# dw08aRev2.net
KiCad netlist of a schematic drawn in EAGLE
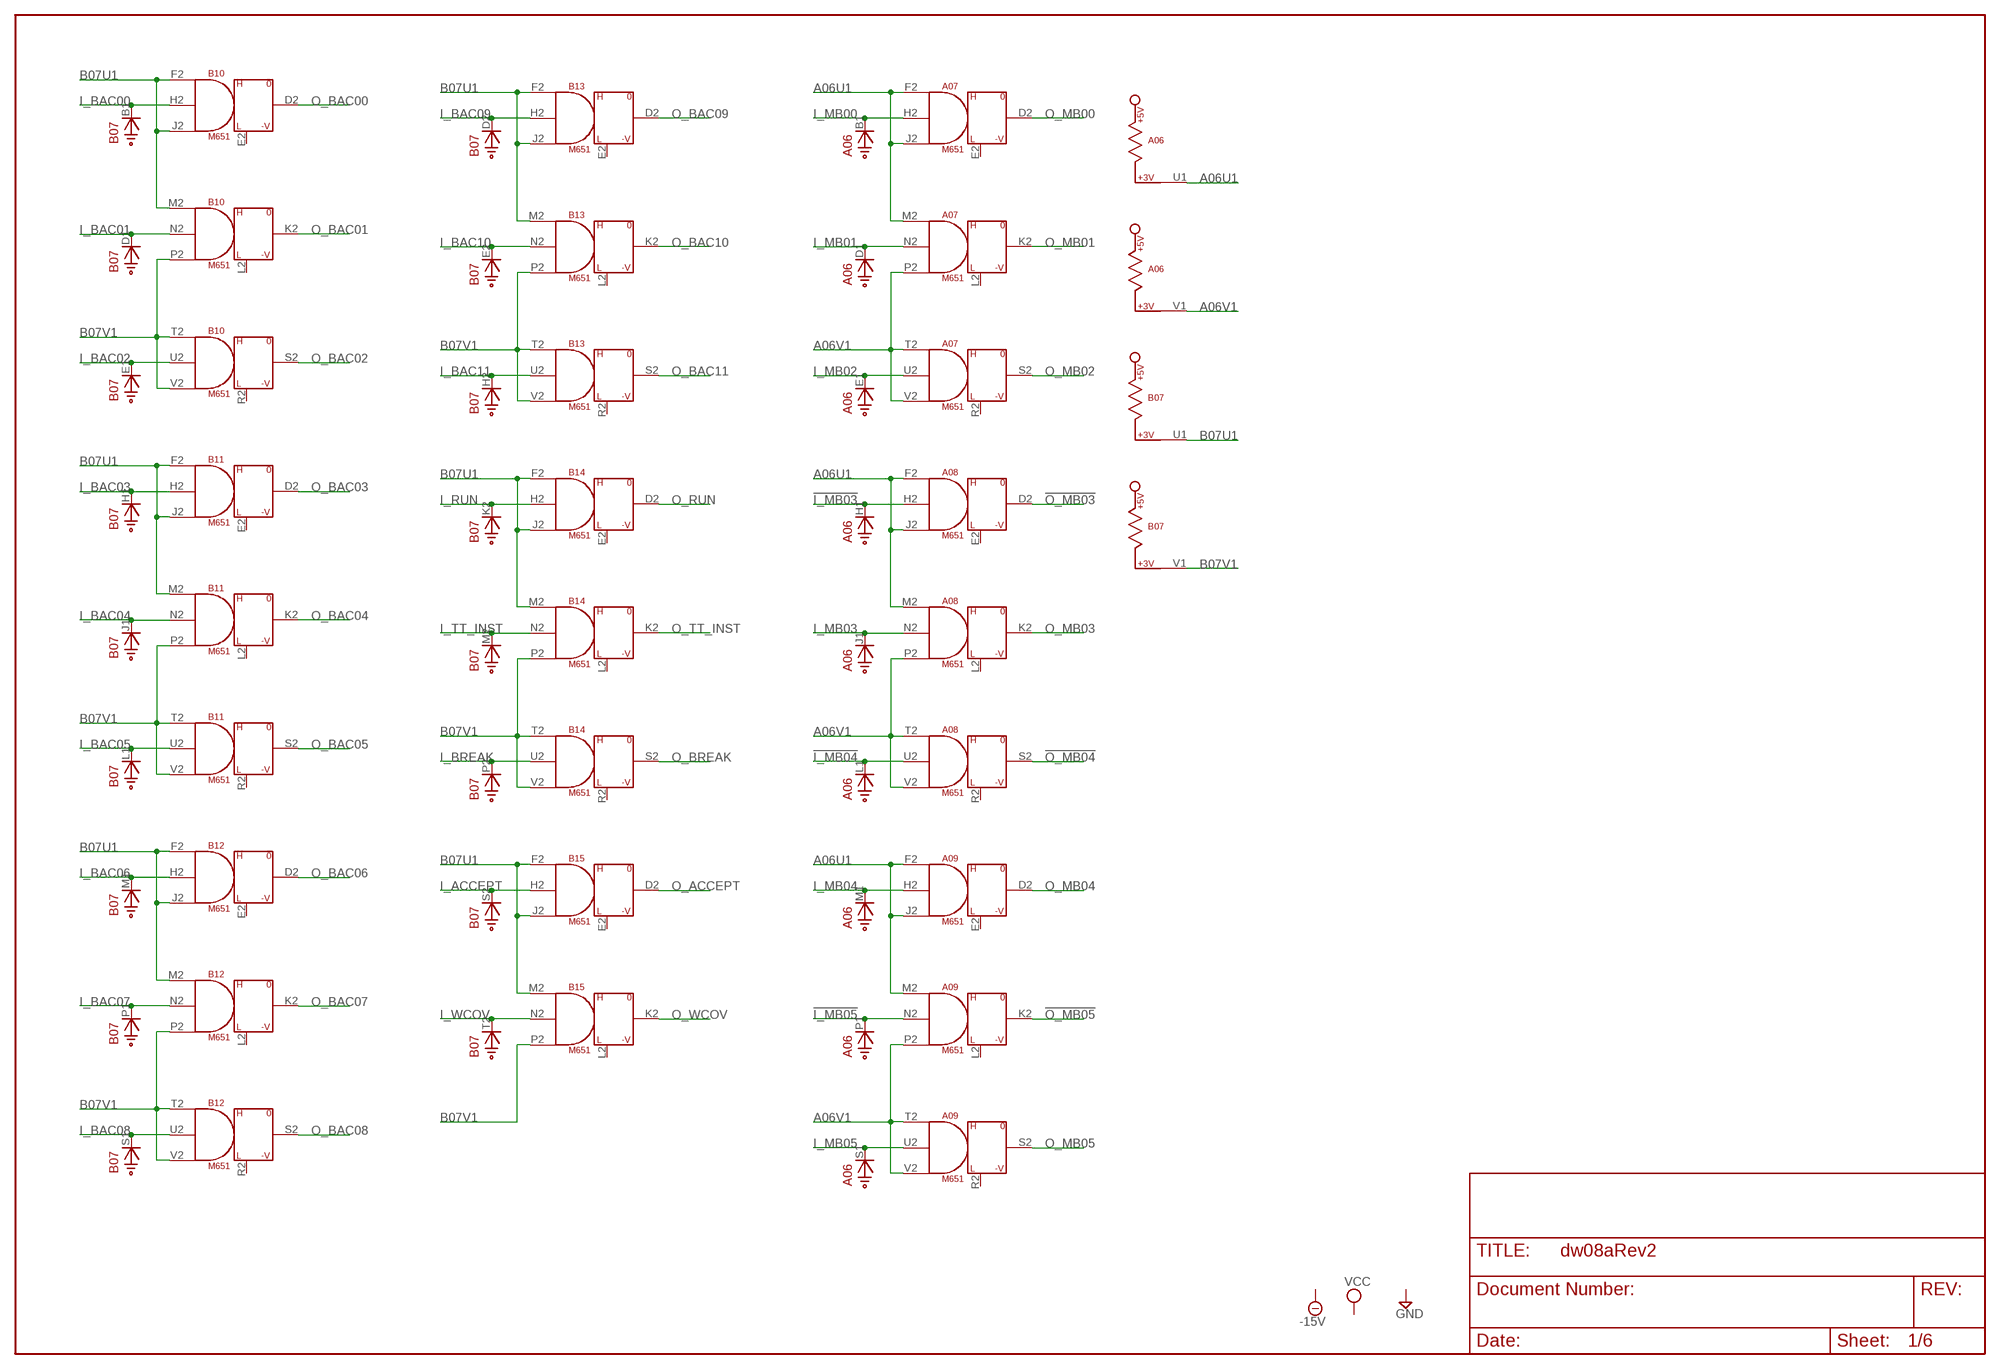
[diagram p0: schematic, sheet 1]
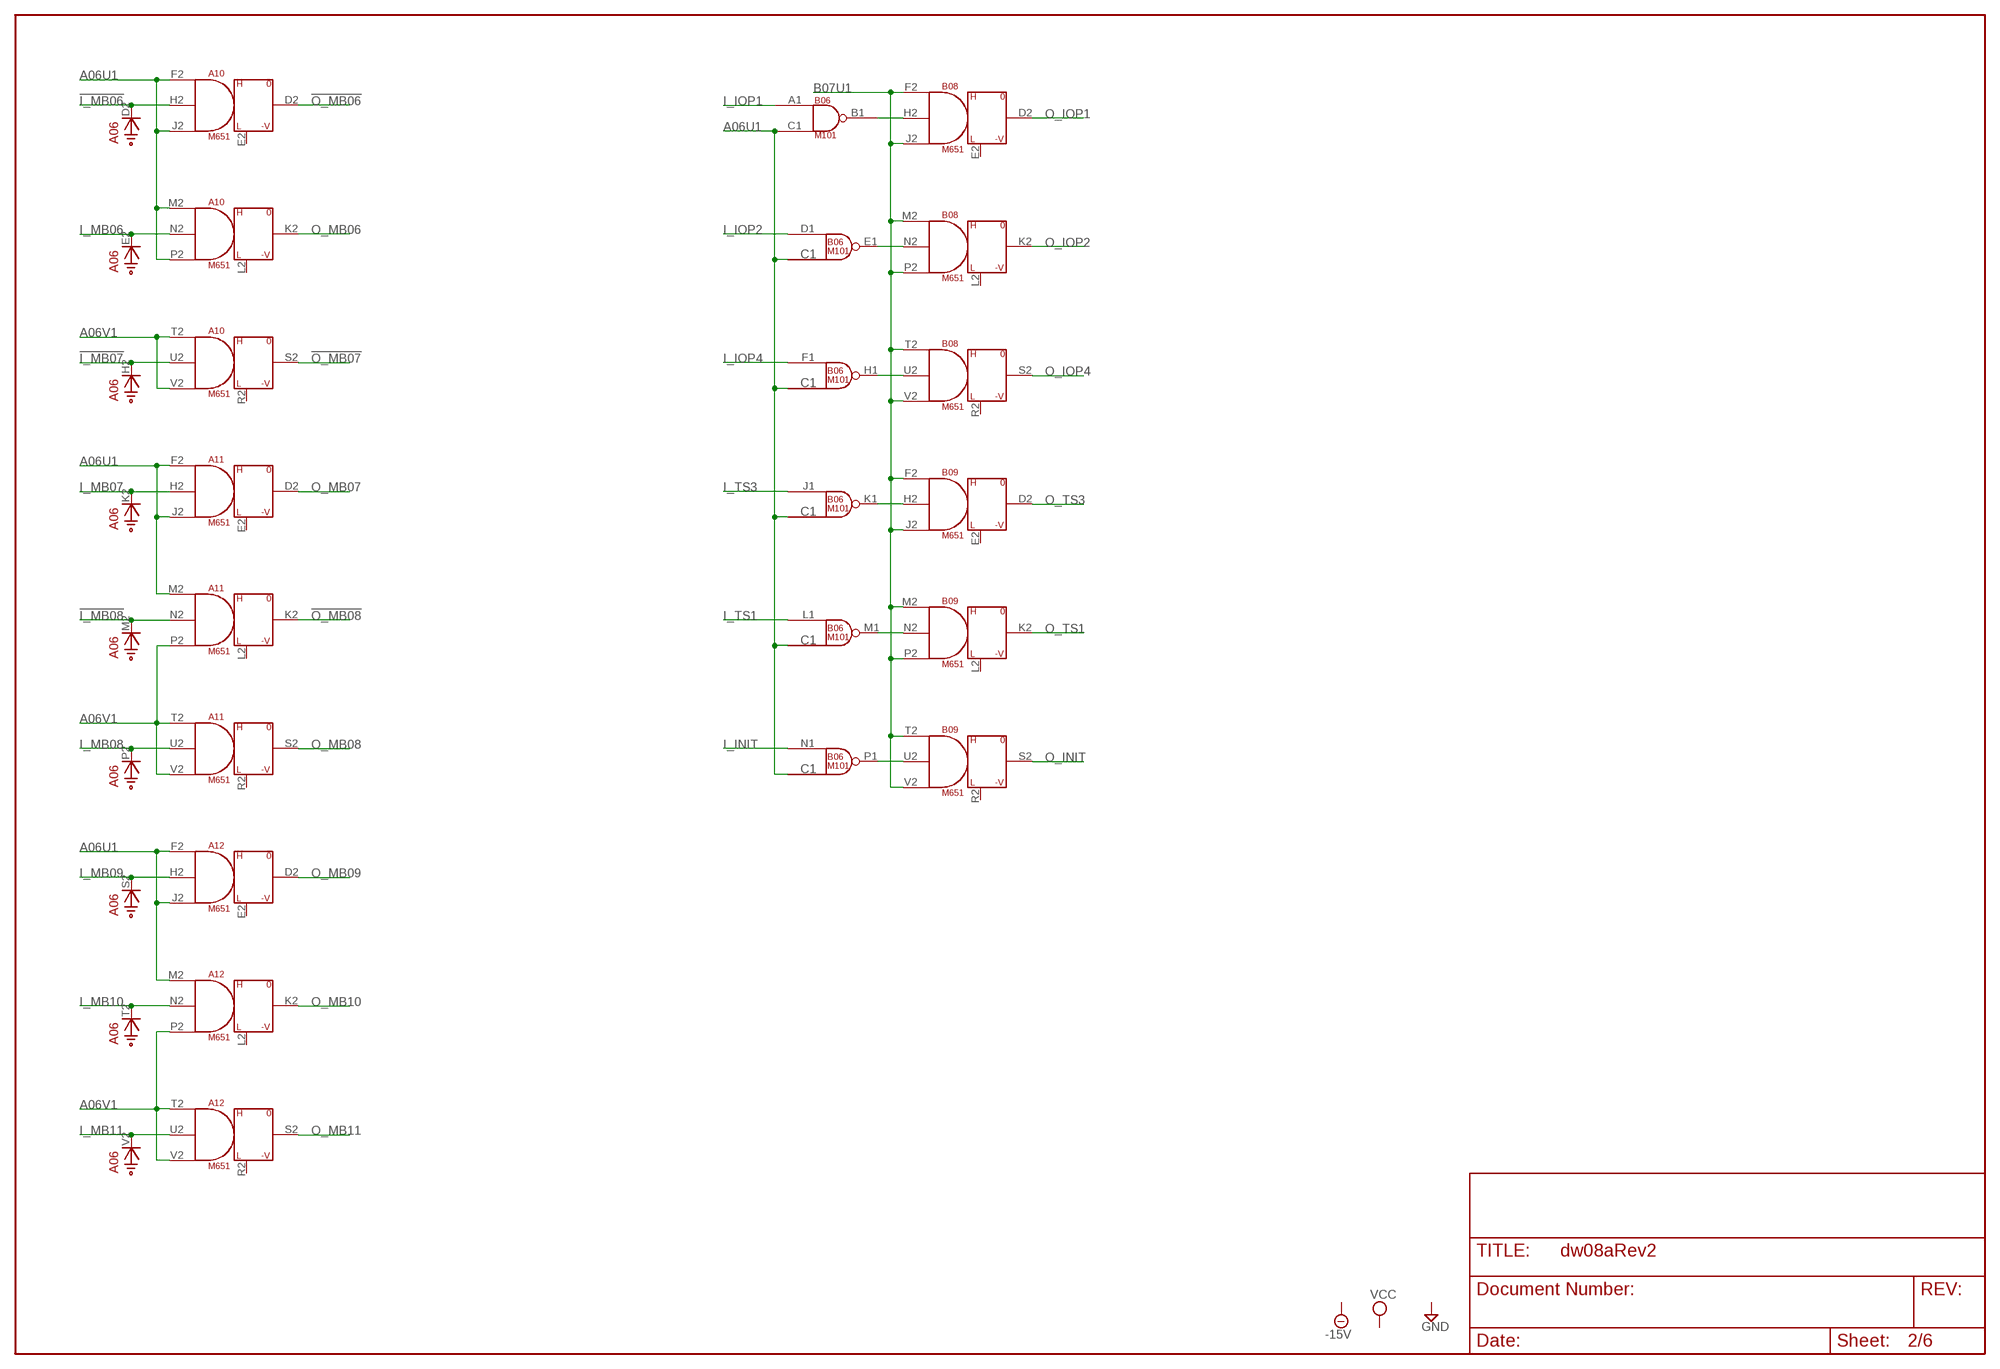
[diagram p1: schematic, sheet 2]
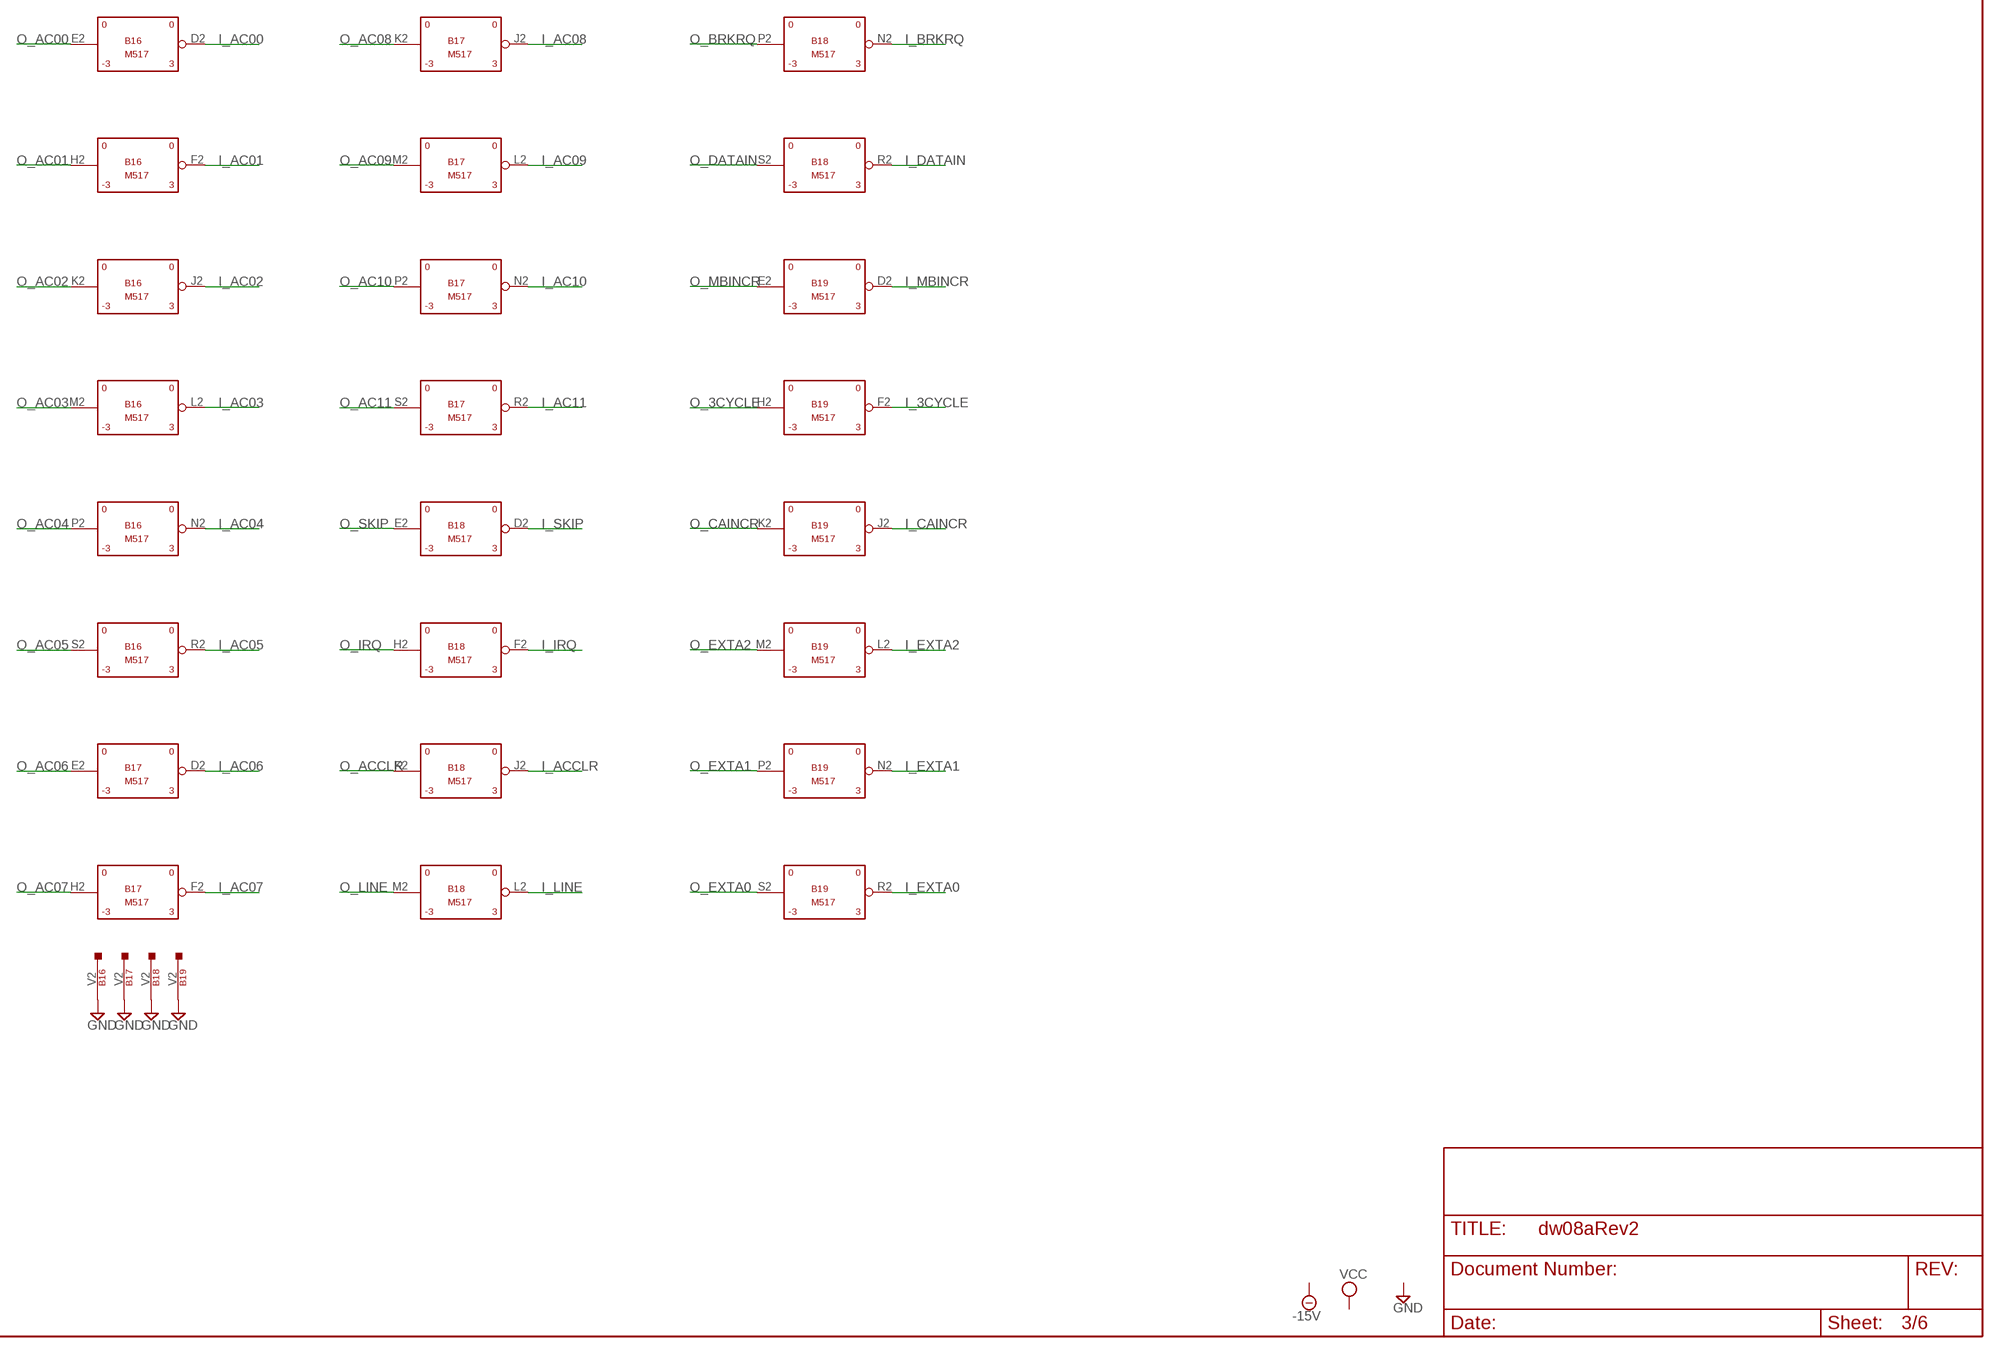
[diagram p2: schematic, sheet 3]
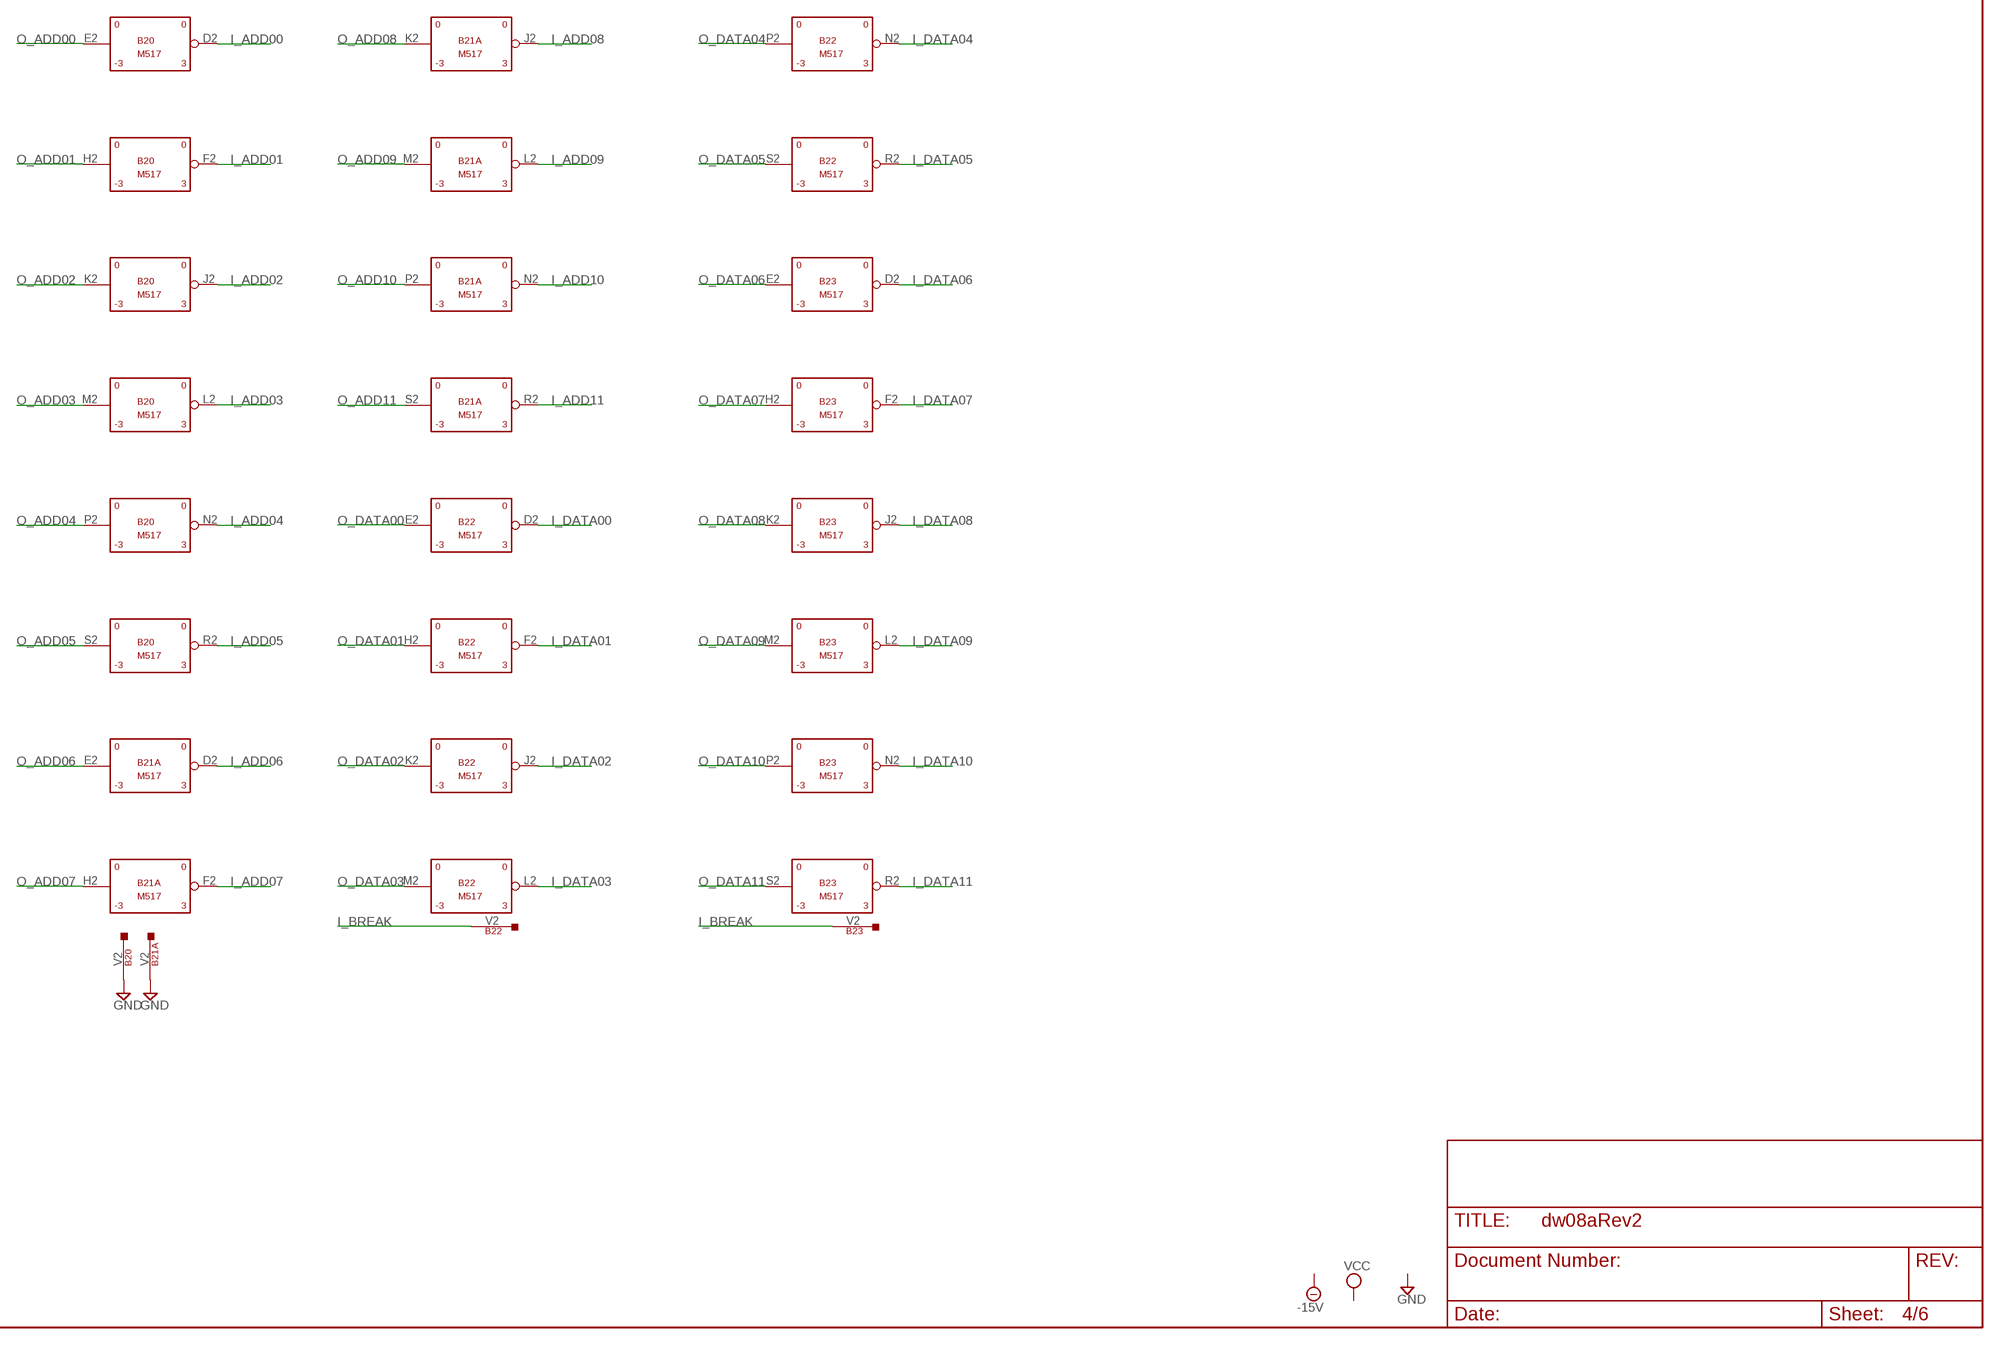
[diagram p3: schematic, sheet 4]
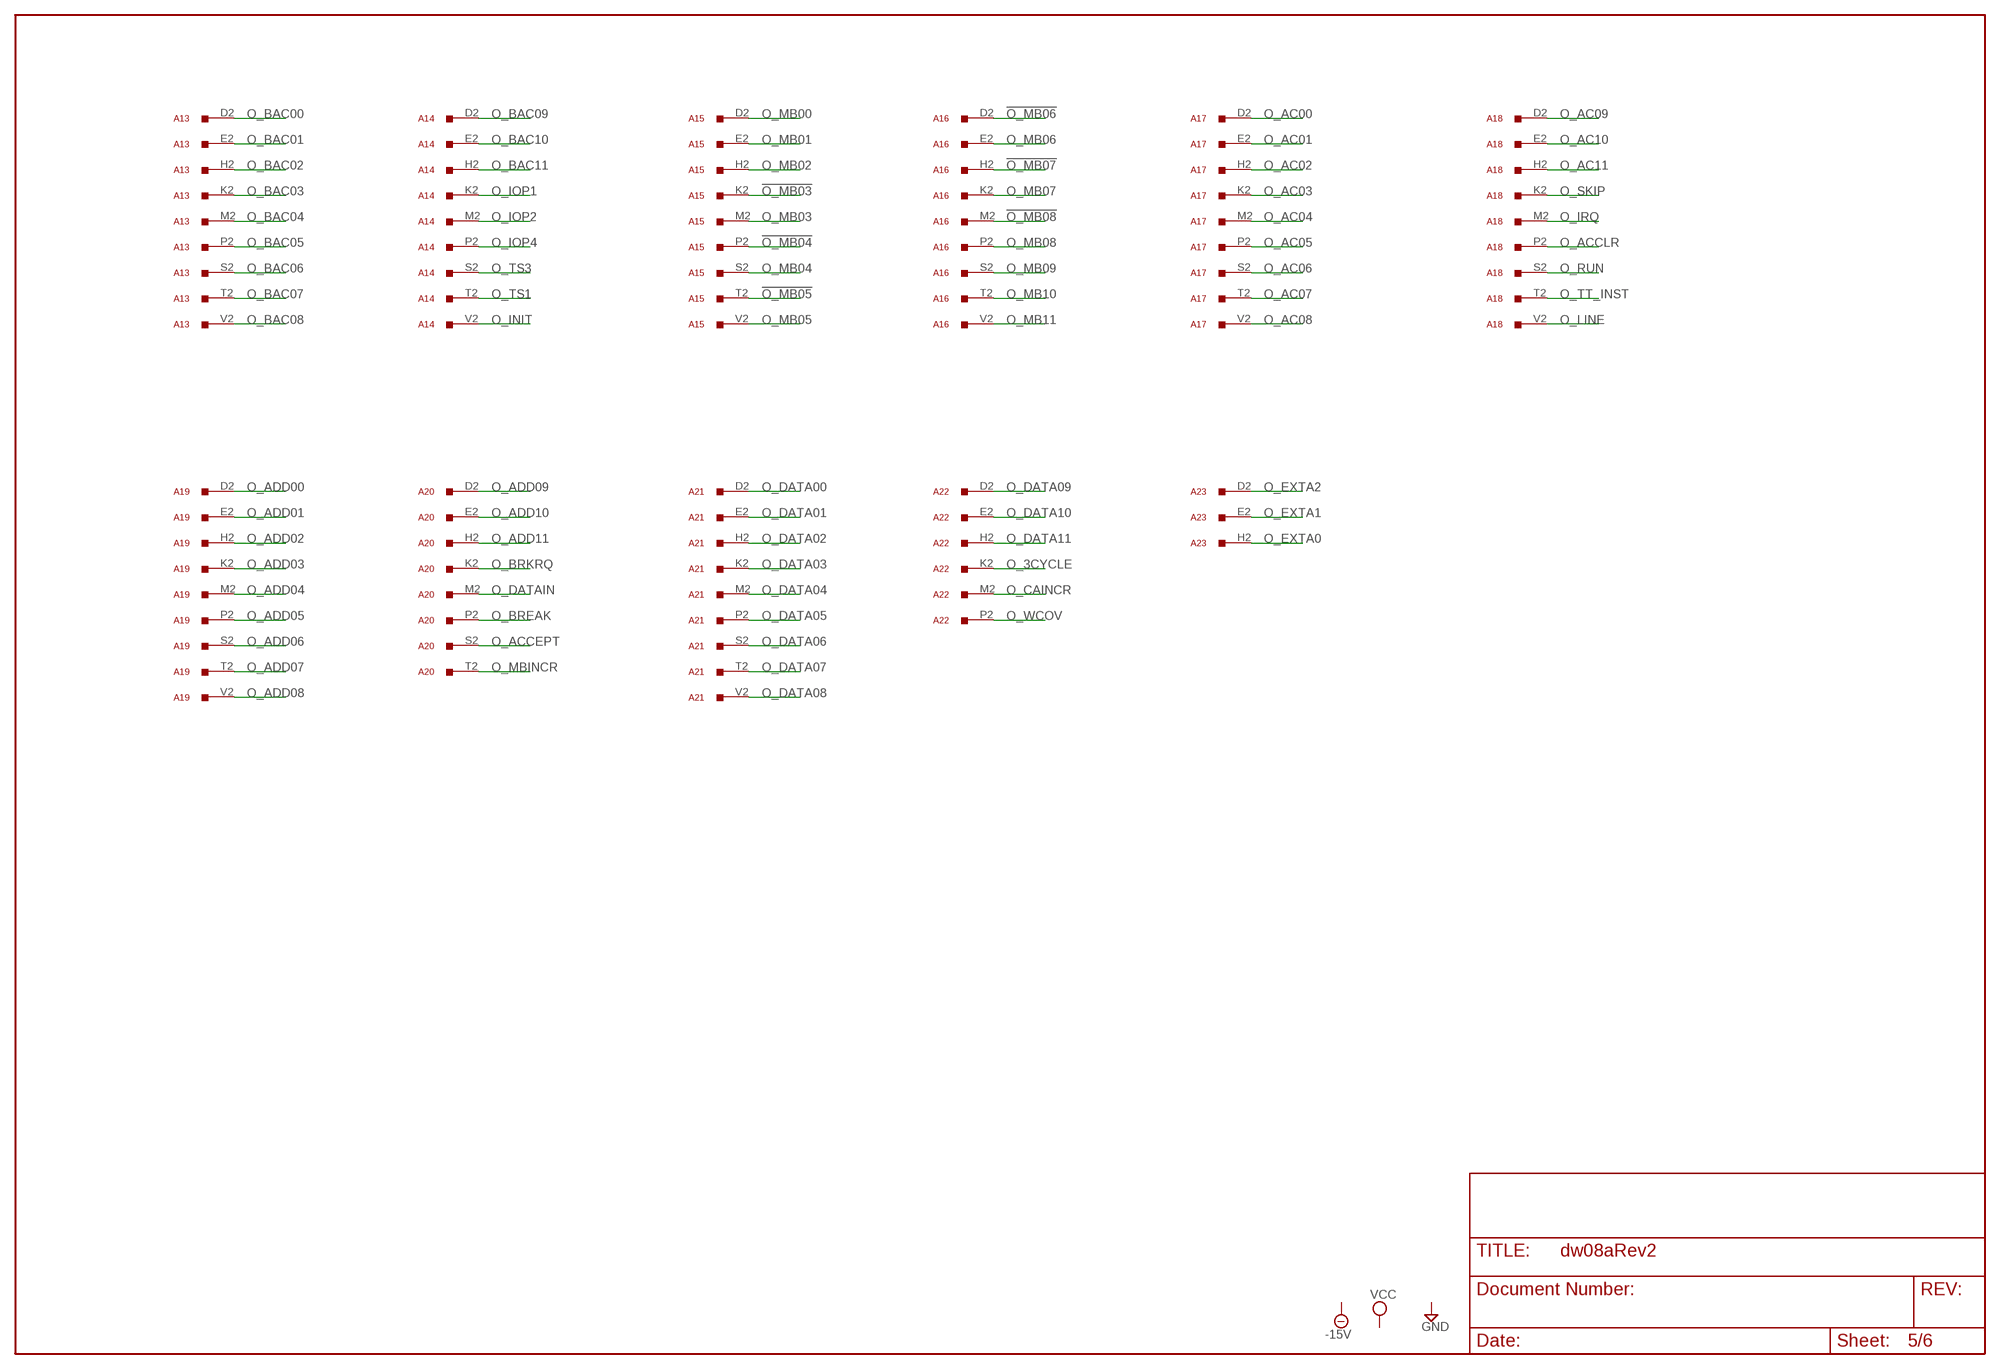
[diagram p4: schematic, sheet 5]
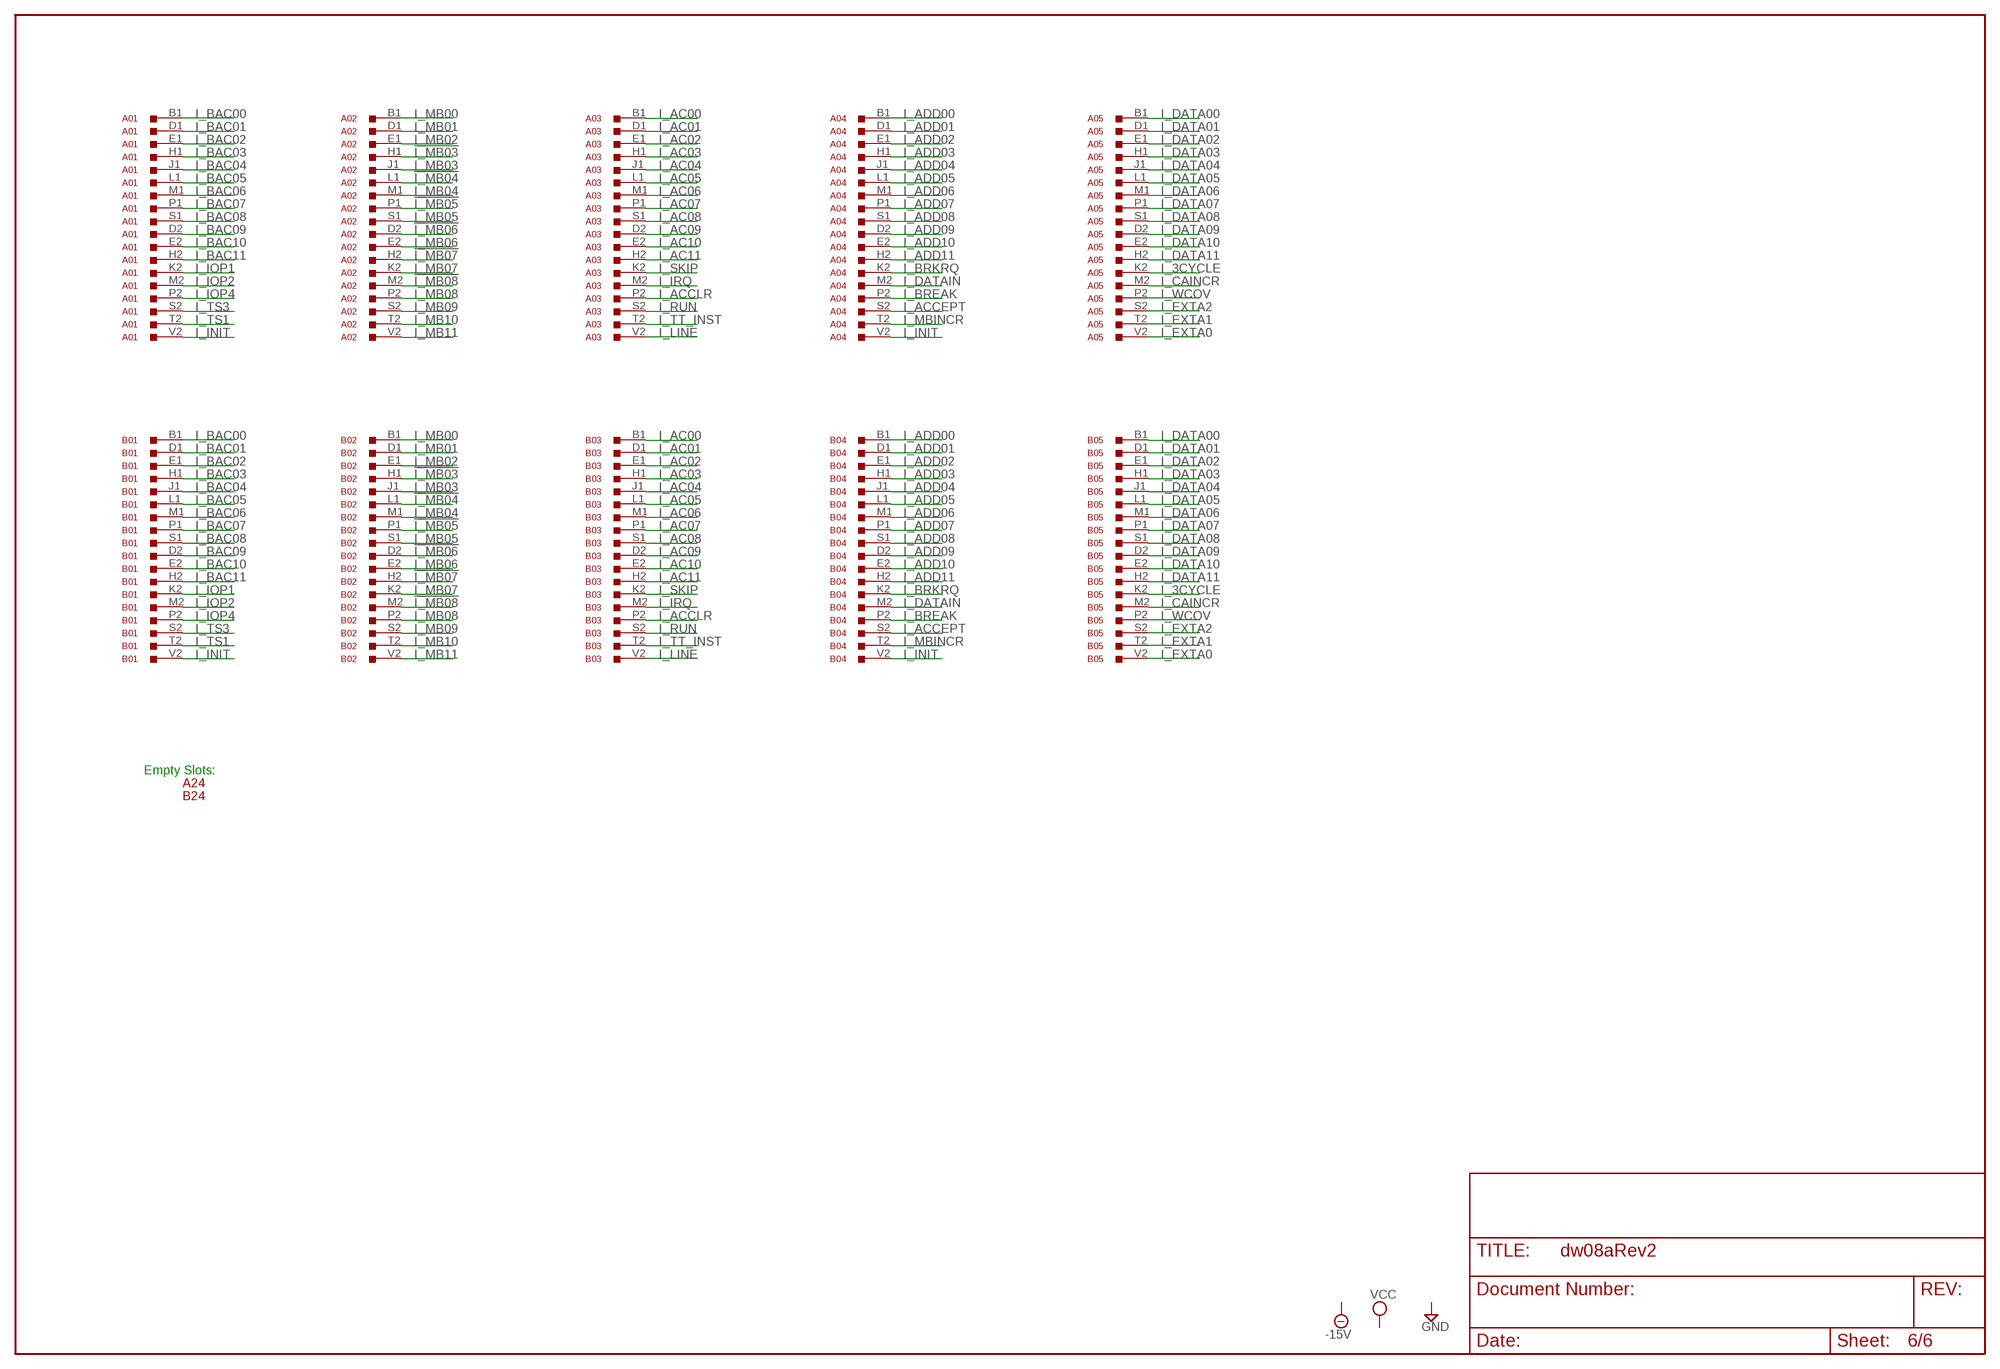
[diagram p5: schematic, sheet 6]

(export (version "E")
  (design (tool "Eeschema 10.0.6"))
  (components
    (comp (ref "A06")
      (value "M907")
      (footprint "eagle-import:H807")
      (libsource (lib "eagle-import") (part "M907"))
    )
    (comp (ref "A07")
      (value "M651")
      (footprint "eagle-import:H807")
      (libsource (lib "eagle-import") (part "M651"))
    )
    (comp (ref "A08")
      (value "M651")
      (footprint "eagle-import:H807")
      (libsource (lib "eagle-import") (part "M651"))
    )
    (comp (ref "A09")
      (value "M651")
      (footprint "eagle-import:H807")
      (libsource (lib "eagle-import") (part "M651"))
    )
    (comp (ref "B07")
      (value "M907")
      (footprint "eagle-import:H807")
      (libsource (lib "eagle-import") (part "M907"))
    )
    (comp (ref "B10")
      (value "M651")
      (footprint "eagle-import:H807")
      (libsource (lib "eagle-import") (part "M651"))
    )
    (comp (ref "B11")
      (value "M651")
      (footprint "eagle-import:H807")
      (libsource (lib "eagle-import") (part "M651"))
    )
    (comp (ref "B12")
      (value "M651")
      (footprint "eagle-import:H807")
      (libsource (lib "eagle-import") (part "M651"))
    )
    (comp (ref "B13")
      (value "M651")
      (footprint "eagle-import:H807")
      (libsource (lib "eagle-import") (part "M651"))
    )
    (comp (ref "B14")
      (value "M651")
      (footprint "eagle-import:H807")
      (libsource (lib "eagle-import") (part "M651"))
    )
    (comp (ref "B15")
      (value "M651")
      (footprint "eagle-import:H807")
      (libsource (lib "eagle-import") (part "M651"))
    )
    (comp (ref "A10")
      (value "M651")
      (footprint "eagle-import:H807")
      (libsource (lib "eagle-import") (part "M651"))
    )
    (comp (ref "A11")
      (value "M651")
      (footprint "eagle-import:H807")
      (libsource (lib "eagle-import") (part "M651"))
    )
    (comp (ref "A12")
      (value "M651")
      (footprint "eagle-import:H807")
      (libsource (lib "eagle-import") (part "M651"))
    )
    (comp (ref "B06")
      (value "M101")
      (footprint "eagle-import:H807")
      (libsource (lib "eagle-import") (part "M101"))
    )
    (comp (ref "B08")
      (value "M651")
      (footprint "eagle-import:H807")
      (libsource (lib "eagle-import") (part "M651"))
    )
    (comp (ref "B09")
      (value "M651")
      (footprint "eagle-import:H807")
      (libsource (lib "eagle-import") (part "M651"))
    )
    (comp (ref "B16")
      (value "M517")
      (footprint "eagle-import:H807")
      (libsource (lib "eagle-import") (part "M517"))
    )
    (comp (ref "B17")
      (value "M517")
      (footprint "eagle-import:H807")
      (libsource (lib "eagle-import") (part "M517"))
    )
    (comp (ref "B18")
      (value "M517")
      (footprint "eagle-import:H807")
      (libsource (lib "eagle-import") (part "M517"))
    )
    (comp (ref "B19")
      (value "M517")
      (footprint "eagle-import:H807")
      (libsource (lib "eagle-import") (part "M517"))
    )
    (comp (ref "A13")
      (value "W011")
      (footprint "eagle-import:H807")
      (libsource (lib "eagle-import") (part "W011"))
    )
    (comp (ref "A14")
      (value "W011")
      (footprint "eagle-import:H807")
      (libsource (lib "eagle-import") (part "W011"))
    )
    (comp (ref "A15")
      (value "W011")
      (footprint "eagle-import:H807")
      (libsource (lib "eagle-import") (part "W011"))
    )
    (comp (ref "A16")
      (value "W011")
      (footprint "eagle-import:H807")
      (libsource (lib "eagle-import") (part "W011"))
    )
    (comp (ref "A17")
      (value "W011")
      (footprint "eagle-import:H807")
      (libsource (lib "eagle-import") (part "W011"))
    )
    (comp (ref "A18")
      (value "W011")
      (footprint "eagle-import:H807")
      (libsource (lib "eagle-import") (part "W011"))
    )
    (comp (ref "A19")
      (value "W011")
      (footprint "eagle-import:H807")
      (libsource (lib "eagle-import") (part "W011"))
    )
    (comp (ref "A20")
      (value "W011")
      (footprint "eagle-import:H807")
      (libsource (lib "eagle-import") (part "W011"))
    )
    (comp (ref "A21")
      (value "W011")
      (footprint "eagle-import:H807")
      (libsource (lib "eagle-import") (part "W011"))
    )
    (comp (ref "A22")
      (value "W011")
      (footprint "eagle-import:H807")
      (libsource (lib "eagle-import") (part "W011"))
    )
    (comp (ref "A23")
      (value "W011")
      (footprint "eagle-import:H807")
      (libsource (lib "eagle-import") (part "W011"))
    )
    (comp (ref "A01")
      (value "M903")
      (footprint "eagle-import:H807")
      (libsource (lib "eagle-import") (part "M903"))
    )
    (comp (ref "A02")
      (value "M903")
      (footprint "eagle-import:H807")
      (libsource (lib "eagle-import") (part "M903"))
    )
    (comp (ref "A03")
      (value "M903")
      (footprint "eagle-import:H807")
      (libsource (lib "eagle-import") (part "M903"))
    )
    (comp (ref "A04")
      (value "M903")
      (footprint "eagle-import:H807")
      (libsource (lib "eagle-import") (part "M903"))
    )
    (comp (ref "A05")
      (value "M903")
      (footprint "eagle-import:H807")
      (libsource (lib "eagle-import") (part "M903"))
    )
    (comp (ref "A24")
      (value "H807")
      (footprint "eagle-import:H807")
      (libsource (lib "eagle-import") (part "H807"))
    )
    (comp (ref "B01")
      (value "M903")
      (footprint "eagle-import:H807")
      (libsource (lib "eagle-import") (part "M903"))
    )
    (comp (ref "B02")
      (value "M903")
      (footprint "eagle-import:H807")
      (libsource (lib "eagle-import") (part "M903"))
    )
    (comp (ref "B03")
      (value "M903")
      (footprint "eagle-import:H807")
      (libsource (lib "eagle-import") (part "M903"))
    )
    (comp (ref "B04")
      (value "M903")
      (footprint "eagle-import:H807")
      (libsource (lib "eagle-import") (part "M903"))
    )
    (comp (ref "B05")
      (value "M903")
      (footprint "eagle-import:H807")
      (libsource (lib "eagle-import") (part "M903"))
    )
    (comp (ref "B24")
      (value "H807")
      (footprint "eagle-import:H807")
      (libsource (lib "eagle-import") (part "H807"))
    )
    (comp (ref "B20")
      (value "M517")
      (footprint "eagle-import:H807")
      (libsource (lib "eagle-import") (part "M517"))
    )
    (comp (ref "B21A")
      (value "M517")
      (footprint "eagle-import:H807")
      (libsource (lib "eagle-import") (part "M517"))
    )
    (comp (ref "B22")
      (value "M517")
      (footprint "eagle-import:H807")
      (libsource (lib "eagle-import") (part "M517"))
    )
    (comp (ref "B23")
      (value "M517")
      (footprint "eagle-import:H807")
      (libsource (lib "eagle-import") (part "M517"))
    )
  )
  (nets
    (net (code "2") (name "A06U1") (class "Default")
      (node (ref "A06") (pin "U1") (pinfunction "P$1_U1") (pintype "passive"))
      (node (ref "A07") (pin "F2") (pinfunction "IN1_F2") (pintype "input"))
      (node (ref "A07") (pin "J2") (pinfunction "IN3_J2") (pintype "input"))
      (node (ref "A07") (pin "M2") (pinfunction "IN1_M2") (pintype "input"))
      (node (ref "A08") (pin "F2") (pinfunction "IN1_F2") (pintype "input"))
      (node (ref "A08") (pin "J2") (pinfunction "IN3_J2") (pintype "input"))
      (node (ref "A08") (pin "M2") (pinfunction "IN1_M2") (pintype "input"))
      (node (ref "A09") (pin "F2") (pinfunction "IN1_F2") (pintype "input"))
      (node (ref "A09") (pin "J2") (pinfunction "IN3_J2") (pintype "input"))
      (node (ref "A09") (pin "M2") (pinfunction "IN1_M2") (pintype "input"))
      (node (ref "A10") (pin "F2") (pinfunction "IN1_F2") (pintype "input"))
      (node (ref "A10") (pin "J2") (pinfunction "IN3_J2") (pintype "input"))
      (node (ref "A10") (pin "M2") (pinfunction "IN1_M2") (pintype "input"))
      (node (ref "A10") (pin "P2") (pinfunction "IN3_P2") (pintype "input"))
      (node (ref "A11") (pin "F2") (pinfunction "IN1_F2") (pintype "input"))
      (node (ref "A11") (pin "J2") (pinfunction "IN3_J2") (pintype "input"))
      (node (ref "A11") (pin "M2") (pinfunction "IN1_M2") (pintype "input"))
      (node (ref "A12") (pin "F2") (pinfunction "IN1_F2") (pintype "input"))
      (node (ref "A12") (pin "J2") (pinfunction "IN3_J2") (pintype "input"))
      (node (ref "A12") (pin "M2") (pinfunction "IN1_M2") (pintype "input"))
      (node (ref "B06") (pin "C1") (pinfunction "IN2_C1") (pintype "input"))
    )
    (net (code "3") (name "A06V1") (class "Default")
      (node (ref "A06") (pin "V1") (pinfunction "P$1_V1") (pintype "passive"))
      (node (ref "A07") (pin "P2") (pinfunction "IN3_P2") (pintype "input"))
      (node (ref "A07") (pin "T2") (pinfunction "IN1_T2") (pintype "input"))
      (node (ref "A07") (pin "V2") (pinfunction "IN3_V2") (pintype "input"))
      (node (ref "A08") (pin "P2") (pinfunction "IN3_P2") (pintype "input"))
      (node (ref "A08") (pin "T2") (pinfunction "IN1_T2") (pintype "input"))
      (node (ref "A08") (pin "V2") (pinfunction "IN3_V2") (pintype "input"))
      (node (ref "A09") (pin "P2") (pinfunction "IN3_P2") (pintype "input"))
      (node (ref "A09") (pin "T2") (pinfunction "IN1_T2") (pintype "input"))
      (node (ref "A09") (pin "V2") (pinfunction "IN3_V2") (pintype "input"))
      (node (ref "A10") (pin "T2") (pinfunction "IN1_T2") (pintype "input"))
      (node (ref "A10") (pin "V2") (pinfunction "IN3_V2") (pintype "input"))
      (node (ref "A11") (pin "P2") (pinfunction "IN3_P2") (pintype "input"))
      (node (ref "A11") (pin "T2") (pinfunction "IN1_T2") (pintype "input"))
      (node (ref "A11") (pin "V2") (pinfunction "IN3_V2") (pintype "input"))
      (node (ref "A12") (pin "P2") (pinfunction "IN3_P2") (pintype "input"))
      (node (ref "A12") (pin "T2") (pinfunction "IN1_T2") (pintype "input"))
      (node (ref "A12") (pin "V2") (pinfunction "IN3_V2") (pintype "input"))
    )
    (net (code "4") (name "B07U1") (class "Default")
      (node (ref "B07") (pin "U1") (pinfunction "P$1_U1") (pintype "passive"))
      (node (ref "B08") (pin "F2") (pinfunction "IN1_F2") (pintype "input"))
      (node (ref "B08") (pin "J2") (pinfunction "IN3_J2") (pintype "input"))
      (node (ref "B08") (pin "M2") (pinfunction "IN1_M2") (pintype "input"))
      (node (ref "B08") (pin "P2") (pinfunction "IN3_P2") (pintype "input"))
      (node (ref "B08") (pin "T2") (pinfunction "IN1_T2") (pintype "input"))
      (node (ref "B08") (pin "V2") (pinfunction "IN3_V2") (pintype "input"))
      (node (ref "B09") (pin "F2") (pinfunction "IN1_F2") (pintype "input"))
      (node (ref "B09") (pin "J2") (pinfunction "IN3_J2") (pintype "input"))
      (node (ref "B09") (pin "M2") (pinfunction "IN1_M2") (pintype "input"))
      (node (ref "B09") (pin "P2") (pinfunction "IN3_P2") (pintype "input"))
      (node (ref "B09") (pin "T2") (pinfunction "IN1_T2") (pintype "input"))
      (node (ref "B09") (pin "V2") (pinfunction "IN3_V2") (pintype "input"))
      (node (ref "B10") (pin "F2") (pinfunction "IN1_F2") (pintype "input"))
      (node (ref "B10") (pin "J2") (pinfunction "IN3_J2") (pintype "input"))
      (node (ref "B10") (pin "M2") (pinfunction "IN1_M2") (pintype "input"))
      (node (ref "B11") (pin "F2") (pinfunction "IN1_F2") (pintype "input"))
      (node (ref "B11") (pin "J2") (pinfunction "IN3_J2") (pintype "input"))
      (node (ref "B11") (pin "M2") (pinfunction "IN1_M2") (pintype "input"))
      (node (ref "B12") (pin "F2") (pinfunction "IN1_F2") (pintype "input"))
      (node (ref "B12") (pin "J2") (pinfunction "IN3_J2") (pintype "input"))
      (node (ref "B12") (pin "M2") (pinfunction "IN1_M2") (pintype "input"))
      (node (ref "B13") (pin "F2") (pinfunction "IN1_F2") (pintype "input"))
      (node (ref "B13") (pin "J2") (pinfunction "IN3_J2") (pintype "input"))
      (node (ref "B13") (pin "M2") (pinfunction "IN1_M2") (pintype "input"))
      (node (ref "B14") (pin "F2") (pinfunction "IN1_F2") (pintype "input"))
      (node (ref "B14") (pin "J2") (pinfunction "IN3_J2") (pintype "input"))
      (node (ref "B14") (pin "M2") (pinfunction "IN1_M2") (pintype "input"))
      (node (ref "B15") (pin "F2") (pinfunction "IN1_F2") (pintype "input"))
      (node (ref "B15") (pin "J2") (pinfunction "IN3_J2") (pintype "input"))
      (node (ref "B15") (pin "M2") (pinfunction "IN1_M2") (pintype "input"))
    )
    (net (code "5") (name "B07V1") (class "Default")
      (node (ref "B07") (pin "V1") (pinfunction "P$1_V1") (pintype "passive"))
      (node (ref "B10") (pin "P2") (pinfunction "IN3_P2") (pintype "input"))
      (node (ref "B10") (pin "T2") (pinfunction "IN1_T2") (pintype "input"))
      (node (ref "B10") (pin "V2") (pinfunction "IN3_V2") (pintype "input"))
      (node (ref "B11") (pin "P2") (pinfunction "IN3_P2") (pintype "input"))
      (node (ref "B11") (pin "T2") (pinfunction "IN1_T2") (pintype "input"))
      (node (ref "B11") (pin "V2") (pinfunction "IN3_V2") (pintype "input"))
      (node (ref "B12") (pin "P2") (pinfunction "IN3_P2") (pintype "input"))
      (node (ref "B12") (pin "T2") (pinfunction "IN1_T2") (pintype "input"))
      (node (ref "B12") (pin "V2") (pinfunction "IN3_V2") (pintype "input"))
      (node (ref "B13") (pin "P2") (pinfunction "IN3_P2") (pintype "input"))
      (node (ref "B13") (pin "T2") (pinfunction "IN1_T2") (pintype "input"))
      (node (ref "B13") (pin "V2") (pinfunction "IN3_V2") (pintype "input"))
      (node (ref "B14") (pin "P2") (pinfunction "IN3_P2") (pintype "input"))
      (node (ref "B14") (pin "T2") (pinfunction "IN1_T2") (pintype "input"))
      (node (ref "B14") (pin "V2") (pinfunction "IN3_V2") (pintype "input"))
      (node (ref "B15") (pin "P2") (pinfunction "IN3_P2") (pintype "input"))
    )
    (net (code "6") (name "GND") (class "Default")
      (node (ref "B16") (pin "V2") (pinfunction "P$1_V2") (pintype "input"))
      (node (ref "B17") (pin "V2") (pinfunction "P$1_V2") (pintype "input"))
      (node (ref "B18") (pin "V2") (pinfunction "P$1_V2") (pintype "input"))
      (node (ref "B19") (pin "V2") (pinfunction "P$1_V2") (pintype "input"))
      (node (ref "B20") (pin "V2") (pinfunction "P$1_V2") (pintype "input"))
      (node (ref "B21A") (pin "V2") (pinfunction "P$1_V2") (pintype "input"))
    )
    (net (code "7") (name "I_3CYCLE") (class "Default")
      (node (ref "A05") (pin "K2") (pinfunction "P$2_K2") (pintype "bidirectional"))
      (node (ref "B05") (pin "K2") (pinfunction "P$2_K2") (pintype "bidirectional"))
      (node (ref "B19") (pin "F2") (pinfunction "OUT_F2") (pintype "output"))
    )
    (net (code "8") (name "I_AC00") (class "Default")
      (node (ref "A03") (pin "B1") (pinfunction "P$2_B1") (pintype "bidirectional"))
      (node (ref "B03") (pin "B1") (pinfunction "P$2_B1") (pintype "bidirectional"))
      (node (ref "B16") (pin "D2") (pinfunction "OUT_D2") (pintype "output"))
    )
    (net (code "9") (name "I_AC01") (class "Default")
      (node (ref "A03") (pin "D1") (pinfunction "P$2_D1") (pintype "bidirectional"))
      (node (ref "B03") (pin "D1") (pinfunction "P$2_D1") (pintype "bidirectional"))
      (node (ref "B16") (pin "F2") (pinfunction "OUT_F2") (pintype "output"))
    )
    (net (code "10") (name "I_AC02") (class "Default")
      (node (ref "A03") (pin "E1") (pinfunction "P$2_E1") (pintype "bidirectional"))
      (node (ref "B03") (pin "E1") (pinfunction "P$2_E1") (pintype "bidirectional"))
      (node (ref "B16") (pin "J2") (pinfunction "OUT_J2") (pintype "output"))
    )
    (net (code "11") (name "I_AC03") (class "Default")
      (node (ref "A03") (pin "H1") (pinfunction "P$2_H1") (pintype "bidirectional"))
      (node (ref "B03") (pin "H1") (pinfunction "P$2_H1") (pintype "bidirectional"))
      (node (ref "B16") (pin "L2") (pinfunction "OUT_L2") (pintype "output"))
    )
    (net (code "12") (name "I_AC04") (class "Default")
      (node (ref "A03") (pin "J1") (pinfunction "P$2_J1") (pintype "bidirectional"))
      (node (ref "B03") (pin "J1") (pinfunction "P$2_J1") (pintype "bidirectional"))
      (node (ref "B16") (pin "N2") (pinfunction "OUT_N2") (pintype "output"))
    )
    (net (code "13") (name "I_AC05") (class "Default")
      (node (ref "A03") (pin "L1") (pinfunction "P$2_L1") (pintype "bidirectional"))
      (node (ref "B03") (pin "L1") (pinfunction "P$2_L1") (pintype "bidirectional"))
      (node (ref "B16") (pin "R2") (pinfunction "OUT_R2") (pintype "output"))
    )
    (net (code "14") (name "I_AC06") (class "Default")
      (node (ref "A03") (pin "M1") (pinfunction "P$2_M1") (pintype "bidirectional"))
      (node (ref "B03") (pin "M1") (pinfunction "P$2_M1") (pintype "bidirectional"))
      (node (ref "B17") (pin "D2") (pinfunction "OUT_D2") (pintype "output"))
    )
    (net (code "15") (name "I_AC07") (class "Default")
      (node (ref "A03") (pin "P1") (pinfunction "P$2_P1") (pintype "bidirectional"))
      (node (ref "B03") (pin "P1") (pinfunction "P$2_P1") (pintype "bidirectional"))
      (node (ref "B17") (pin "F2") (pinfunction "OUT_F2") (pintype "output"))
    )
    (net (code "16") (name "I_AC08") (class "Default")
      (node (ref "A03") (pin "S1") (pinfunction "P$2_S1") (pintype "bidirectional"))
      (node (ref "B03") (pin "S1") (pinfunction "P$2_S1") (pintype "bidirectional"))
      (node (ref "B17") (pin "J2") (pinfunction "OUT_J2") (pintype "output"))
    )
    (net (code "17") (name "I_AC09") (class "Default")
      (node (ref "A03") (pin "D2") (pinfunction "P$2_D2") (pintype "bidirectional"))
      (node (ref "B03") (pin "D2") (pinfunction "P$2_D2") (pintype "bidirectional"))
      (node (ref "B17") (pin "L2") (pinfunction "OUT_L2") (pintype "output"))
    )
    (net (code "18") (name "I_AC10") (class "Default")
      (node (ref "A03") (pin "E2") (pinfunction "P$2_E2") (pintype "bidirectional"))
      (node (ref "B03") (pin "E2") (pinfunction "P$2_E2") (pintype "bidirectional"))
      (node (ref "B17") (pin "N2") (pinfunction "OUT_N2") (pintype "output"))
    )
    (net (code "19") (name "I_AC11") (class "Default")
      (node (ref "A03") (pin "H2") (pinfunction "P$2_H2") (pintype "bidirectional"))
      (node (ref "B03") (pin "H2") (pinfunction "P$2_H2") (pintype "bidirectional"))
      (node (ref "B17") (pin "R2") (pinfunction "OUT_R2") (pintype "output"))
    )
    (net (code "20") (name "I_ACCEPT") (class "Default")
      (node (ref "A04") (pin "S2") (pinfunction "P$2_S2") (pintype "bidirectional"))
      (node (ref "B04") (pin "S2") (pinfunction "P$2_S2") (pintype "bidirectional"))
      (node (ref "B07") (pin "S2") (pinfunction "CATHODE_S2") (pintype "passive"))
      (node (ref "B15") (pin "H2") (pinfunction "IN2_H2") (pintype "input"))
    )
    (net (code "21") (name "I_ACCLR") (class "Default")
      (node (ref "A03") (pin "P2") (pinfunction "P$2_P2") (pintype "bidirectional"))
      (node (ref "B03") (pin "P2") (pinfunction "P$2_P2") (pintype "bidirectional"))
      (node (ref "B18") (pin "J2") (pinfunction "OUT_J2") (pintype "output"))
    )
    (net (code "22") (name "I_ADD00") (class "Default")
      (node (ref "A04") (pin "B1") (pinfunction "P$2_B1") (pintype "bidirectional"))
      (node (ref "B04") (pin "B1") (pinfunction "P$2_B1") (pintype "bidirectional"))
      (node (ref "B20") (pin "D2") (pinfunction "OUT_D2") (pintype "output"))
    )
    (net (code "23") (name "I_ADD01") (class "Default")
      (node (ref "A04") (pin "D1") (pinfunction "P$2_D1") (pintype "bidirectional"))
      (node (ref "B04") (pin "D1") (pinfunction "P$2_D1") (pintype "bidirectional"))
      (node (ref "B20") (pin "F2") (pinfunction "OUT_F2") (pintype "output"))
    )
    (net (code "24") (name "I_ADD02") (class "Default")
      (node (ref "A04") (pin "E1") (pinfunction "P$2_E1") (pintype "bidirectional"))
      (node (ref "B04") (pin "E1") (pinfunction "P$2_E1") (pintype "bidirectional"))
      (node (ref "B20") (pin "J2") (pinfunction "OUT_J2") (pintype "output"))
    )
    (net (code "25") (name "I_ADD03") (class "Default")
      (node (ref "A04") (pin "H1") (pinfunction "P$2_H1") (pintype "bidirectional"))
      (node (ref "B04") (pin "H1") (pinfunction "P$2_H1") (pintype "bidirectional"))
      (node (ref "B20") (pin "L2") (pinfunction "OUT_L2") (pintype "output"))
    )
    (net (code "26") (name "I_ADD04") (class "Default")
      (node (ref "A04") (pin "J1") (pinfunction "P$2_J1") (pintype "bidirectional"))
      (node (ref "B04") (pin "J1") (pinfunction "P$2_J1") (pintype "bidirectional"))
      (node (ref "B20") (pin "N2") (pinfunction "OUT_N2") (pintype "output"))
    )
    (net (code "27") (name "I_ADD05") (class "Default")
      (node (ref "A04") (pin "L1") (pinfunction "P$2_L1") (pintype "bidirectional"))
      (node (ref "B04") (pin "L1") (pinfunction "P$2_L1") (pintype "bidirectional"))
      (node (ref "B20") (pin "R2") (pinfunction "OUT_R2") (pintype "output"))
    )
    (net (code "28") (name "I_ADD06") (class "Default")
      (node (ref "A04") (pin "M1") (pinfunction "P$2_M1") (pintype "bidirectional"))
      (node (ref "B04") (pin "M1") (pinfunction "P$2_M1") (pintype "bidirectional"))
      (node (ref "B21A") (pin "D2") (pinfunction "OUT_D2") (pintype "output"))
    )
    (net (code "29") (name "I_ADD07") (class "Default")
      (node (ref "A04") (pin "P1") (pinfunction "P$2_P1") (pintype "bidirectional"))
      (node (ref "B04") (pin "P1") (pinfunction "P$2_P1") (pintype "bidirectional"))
      (node (ref "B21A") (pin "F2") (pinfunction "OUT_F2") (pintype "output"))
    )
    (net (code "30") (name "I_ADD08") (class "Default")
      (node (ref "A04") (pin "S1") (pinfunction "P$2_S1") (pintype "bidirectional"))
      (node (ref "B04") (pin "S1") (pinfunction "P$2_S1") (pintype "bidirectional"))
      (node (ref "B21A") (pin "J2") (pinfunction "OUT_J2") (pintype "output"))
    )
    (net (code "31") (name "I_ADD09") (class "Default")
      (node (ref "A04") (pin "D2") (pinfunction "P$2_D2") (pintype "bidirectional"))
      (node (ref "B04") (pin "D2") (pinfunction "P$2_D2") (pintype "bidirectional"))
      (node (ref "B21A") (pin "L2") (pinfunction "OUT_L2") (pintype "output"))
    )
    (net (code "32") (name "I_ADD10") (class "Default")
      (node (ref "A04") (pin "E2") (pinfunction "P$2_E2") (pintype "bidirectional"))
      (node (ref "B04") (pin "E2") (pinfunction "P$2_E2") (pintype "bidirectional"))
      (node (ref "B21A") (pin "N2") (pinfunction "OUT_N2") (pintype "output"))
    )
    (net (code "33") (name "I_ADD11") (class "Default")
      (node (ref "A04") (pin "H2") (pinfunction "P$2_H2") (pintype "bidirectional"))
      (node (ref "B04") (pin "H2") (pinfunction "P$2_H2") (pintype "bidirectional"))
      (node (ref "B21A") (pin "R2") (pinfunction "OUT_R2") (pintype "output"))
    )
    (net (code "34") (name "I_BAC00") (class "Default")
      (node (ref "A01") (pin "B1") (pinfunction "P$2_B1") (pintype "bidirectional"))
      (node (ref "B01") (pin "B1") (pinfunction "P$2_B1") (pintype "bidirectional"))
      (node (ref "B07") (pin "B1") (pinfunction "CATHODE_B1") (pintype "passive"))
      (node (ref "B10") (pin "H2") (pinfunction "IN2_H2") (pintype "input"))
    )
    (net (code "35") (name "I_BAC01") (class "Default")
      (node (ref "A01") (pin "D1") (pinfunction "P$2_D1") (pintype "bidirectional"))
      (node (ref "B01") (pin "D1") (pinfunction "P$2_D1") (pintype "bidirectional"))
      (node (ref "B07") (pin "D1") (pinfunction "CATHODE_D1") (pintype "passive"))
      (node (ref "B10") (pin "N2") (pinfunction "IN2_N2") (pintype "input"))
    )
    (net (code "36") (name "I_BAC02") (class "Default")
      (node (ref "A01") (pin "E1") (pinfunction "P$2_E1") (pintype "bidirectional"))
      (node (ref "B01") (pin "E1") (pinfunction "P$2_E1") (pintype "bidirectional"))
      (node (ref "B07") (pin "E1") (pinfunction "CATHODE_E1") (pintype "passive"))
      (node (ref "B10") (pin "U2") (pinfunction "IN2_U2") (pintype "input"))
    )
    (net (code "37") (name "I_BAC03") (class "Default")
      (node (ref "A01") (pin "H1") (pinfunction "P$2_H1") (pintype "bidirectional"))
      (node (ref "B01") (pin "H1") (pinfunction "P$2_H1") (pintype "bidirectional"))
      (node (ref "B07") (pin "H1") (pinfunction "CATHODE_H1") (pintype "passive"))
      (node (ref "B11") (pin "H2") (pinfunction "IN2_H2") (pintype "input"))
    )
    (net (code "38") (name "I_BAC04") (class "Default")
      (node (ref "A01") (pin "J1") (pinfunction "P$2_J1") (pintype "bidirectional"))
      (node (ref "B01") (pin "J1") (pinfunction "P$2_J1") (pintype "bidirectional"))
      (node (ref "B07") (pin "J1") (pinfunction "CATHODE_J1") (pintype "passive"))
      (node (ref "B11") (pin "N2") (pinfunction "IN2_N2") (pintype "input"))
    )
    (net (code "39") (name "I_BAC05") (class "Default")
      (node (ref "A01") (pin "L1") (pinfunction "P$2_L1") (pintype "bidirectional"))
      (node (ref "B01") (pin "L1") (pinfunction "P$2_L1") (pintype "bidirectional"))
      (node (ref "B07") (pin "L1") (pinfunction "CATHODE_L1") (pintype "passive"))
      (node (ref "B11") (pin "U2") (pinfunction "IN2_U2") (pintype "input"))
    )
    (net (code "40") (name "I_BAC06") (class "Default")
      (node (ref "A01") (pin "M1") (pinfunction "P$2_M1") (pintype "bidirectional"))
      (node (ref "B01") (pin "M1") (pinfunction "P$2_M1") (pintype "bidirectional"))
      (node (ref "B07") (pin "M1") (pinfunction "CATHODE_M1") (pintype "passive"))
      (node (ref "B12") (pin "H2") (pinfunction "IN2_H2") (pintype "input"))
    )
    (net (code "41") (name "I_BAC07") (class "Default")
      (node (ref "A01") (pin "P1") (pinfunction "P$2_P1") (pintype "bidirectional"))
      (node (ref "B01") (pin "P1") (pinfunction "P$2_P1") (pintype "bidirectional"))
      (node (ref "B07") (pin "P1") (pinfunction "CATHODE_P1") (pintype "passive"))
      (node (ref "B12") (pin "N2") (pinfunction "IN2_N2") (pintype "input"))
    )
    (net (code "42") (name "I_BAC08") (class "Default")
      (node (ref "A01") (pin "S1") (pinfunction "P$2_S1") (pintype "bidirectional"))
      (node (ref "B01") (pin "S1") (pinfunction "P$2_S1") (pintype "bidirectional"))
      (node (ref "B07") (pin "S1") (pinfunction "CATHODE_S1") (pintype "passive"))
      (node (ref "B12") (pin "U2") (pinfunction "IN2_U2") (pintype "input"))
    )
    (net (code "43") (name "I_BAC09") (class "Default")
      (node (ref "A01") (pin "D2") (pinfunction "P$2_D2") (pintype "bidirectional"))
      (node (ref "B01") (pin "D2") (pinfunction "P$2_D2") (pintype "bidirectional"))
      (node (ref "B07") (pin "D2") (pinfunction "CATHODE_D2") (pintype "passive"))
      (node (ref "B13") (pin "H2") (pinfunction "IN2_H2") (pintype "input"))
    )
    (net (code "44") (name "I_BAC10") (class "Default")
      (node (ref "A01") (pin "E2") (pinfunction "P$2_E2") (pintype "bidirectional"))
      (node (ref "B01") (pin "E2") (pinfunction "P$2_E2") (pintype "bidirectional"))
      (node (ref "B07") (pin "E2") (pinfunction "CATHODE_E2") (pintype "passive"))
      (node (ref "B13") (pin "N2") (pinfunction "IN2_N2") (pintype "input"))
    )
    (net (code "45") (name "I_BAC11") (class "Default")
      (node (ref "A01") (pin "H2") (pinfunction "P$2_H2") (pintype "bidirectional"))
      (node (ref "B01") (pin "H2") (pinfunction "P$2_H2") (pintype "bidirectional"))
      (node (ref "B07") (pin "H2") (pinfunction "CATHODE_H2") (pintype "passive"))
      (node (ref "B13") (pin "U2") (pinfunction "IN2_U2") (pintype "input"))
    )
    (net (code "46") (name "I_BREAK") (class "Default")
      (node (ref "A04") (pin "P2") (pinfunction "P$2_P2") (pintype "bidirectional"))
      (node (ref "B04") (pin "P2") (pinfunction "P$2_P2") (pintype "bidirectional"))
      (node (ref "B07") (pin "P2") (pinfunction "CATHODE_P2") (pintype "passive"))
      (node (ref "B14") (pin "U2") (pinfunction "IN2_U2") (pintype "input"))
      (node (ref "B22") (pin "V2") (pinfunction "P$1_V2") (pintype "input"))
      (node (ref "B23") (pin "V2") (pinfunction "P$1_V2") (pintype "input"))
    )
    (net (code "47") (name "I_BRKRQ") (class "Default")
      (node (ref "A04") (pin "K2") (pinfunction "P$2_K2") (pintype "bidirectional"))
      (node (ref "B04") (pin "K2") (pinfunction "P$2_K2") (pintype "bidirectional"))
      (node (ref "B18") (pin "N2") (pinfunction "OUT_N2") (pintype "output"))
    )
    (net (code "48") (name "I_CAINCR") (class "Default")
      (node (ref "A05") (pin "M2") (pinfunction "P$2_M2") (pintype "bidirectional"))
      (node (ref "B05") (pin "M2") (pinfunction "P$2_M2") (pintype "bidirectional"))
      (node (ref "B19") (pin "J2") (pinfunction "OUT_J2") (pintype "output"))
    )
    (net (code "49") (name "I_DATA00") (class "Default")
      (node (ref "A05") (pin "B1") (pinfunction "P$2_B1") (pintype "bidirectional"))
      (node (ref "B05") (pin "B1") (pinfunction "P$2_B1") (pintype "bidirectional"))
      (node (ref "B22") (pin "D2") (pinfunction "OUT_D2") (pintype "output"))
    )
    (net (code "50") (name "I_DATA01") (class "Default")
      (node (ref "A05") (pin "D1") (pinfunction "P$2_D1") (pintype "bidirectional"))
      (node (ref "B05") (pin "D1") (pinfunction "P$2_D1") (pintype "bidirectional"))
      (node (ref "B22") (pin "F2") (pinfunction "OUT_F2") (pintype "output"))
    )
    (net (code "51") (name "I_DATA02") (class "Default")
      (node (ref "A05") (pin "E1") (pinfunction "P$2_E1") (pintype "bidirectional"))
      (node (ref "B05") (pin "E1") (pinfunction "P$2_E1") (pintype "bidirectional"))
      (node (ref "B22") (pin "J2") (pinfunction "OUT_J2") (pintype "output"))
    )
    (net (code "52") (name "I_DATA03") (class "Default")
      (node (ref "A05") (pin "H1") (pinfunction "P$2_H1") (pintype "bidirectional"))
      (node (ref "B05") (pin "H1") (pinfunction "P$2_H1") (pintype "bidirectional"))
      (node (ref "B22") (pin "L2") (pinfunction "OUT_L2") (pintype "output"))
    )
    (net (code "53") (name "I_DATA04") (class "Default")
      (node (ref "A05") (pin "J1") (pinfunction "P$2_J1") (pintype "bidirectional"))
      (node (ref "B05") (pin "J1") (pinfunction "P$2_J1") (pintype "bidirectional"))
      (node (ref "B22") (pin "N2") (pinfunction "OUT_N2") (pintype "output"))
    )
    (net (code "54") (name "I_DATA05") (class "Default")
      (node (ref "A05") (pin "L1") (pinfunction "P$2_L1") (pintype "bidirectional"))
      (node (ref "B05") (pin "L1") (pinfunction "P$2_L1") (pintype "bidirectional"))
      (node (ref "B22") (pin "R2") (pinfunction "OUT_R2") (pintype "output"))
    )
    (net (code "55") (name "I_DATA06") (class "Default")
      (node (ref "A05") (pin "M1") (pinfunction "P$2_M1") (pintype "bidirectional"))
      (node (ref "B05") (pin "M1") (pinfunction "P$2_M1") (pintype "bidirectional"))
      (node (ref "B23") (pin "D2") (pinfunction "OUT_D2") (pintype "output"))
    )
    (net (code "56") (name "I_DATA07") (class "Default")
      (node (ref "A05") (pin "P1") (pinfunction "P$2_P1") (pintype "bidirectional"))
      (node (ref "B05") (pin "P1") (pinfunction "P$2_P1") (pintype "bidirectional"))
      (node (ref "B23") (pin "F2") (pinfunction "OUT_F2") (pintype "output"))
    )
    (net (code "57") (name "I_DATA08") (class "Default")
      (node (ref "A05") (pin "S1") (pinfunction "P$2_S1") (pintype "bidirectional"))
      (node (ref "B05") (pin "S1") (pinfunction "P$2_S1") (pintype "bidirectional"))
      (node (ref "B23") (pin "J2") (pinfunction "OUT_J2") (pintype "output"))
    )
    (net (code "58") (name "I_DATA09") (class "Default")
      (node (ref "A05") (pin "D2") (pinfunction "P$2_D2") (pintype "bidirectional"))
      (node (ref "B05") (pin "D2") (pinfunction "P$2_D2") (pintype "bidirectional"))
      (node (ref "B23") (pin "L2") (pinfunction "OUT_L2") (pintype "output"))
    )
    (net (code "59") (name "I_DATA10") (class "Default")
      (node (ref "A05") (pin "E2") (pinfunction "P$2_E2") (pintype "bidirectional"))
      (node (ref "B05") (pin "E2") (pinfunction "P$2_E2") (pintype "bidirectional"))
      (node (ref "B23") (pin "N2") (pinfunction "OUT_N2") (pintype "output"))
    )
    (net (code "60") (name "I_DATA11") (class "Default")
      (node (ref "A05") (pin "H2") (pinfunction "P$2_H2") (pintype "bidirectional"))
      (node (ref "B05") (pin "H2") (pinfunction "P$2_H2") (pintype "bidirectional"))
      (node (ref "B23") (pin "R2") (pinfunction "OUT_R2") (pintype "output"))
    )
    (net (code "61") (name "I_DATAIN") (class "Default")
      (node (ref "A04") (pin "M2") (pinfunction "P$2_M2") (pintype "bidirectional"))
      (node (ref "B04") (pin "M2") (pinfunction "P$2_M2") (pintype "bidirectional"))
      (node (ref "B18") (pin "R2") (pinfunction "OUT_R2") (pintype "output"))
    )
    (net (code "62") (name "I_EXTA0") (class "Default")
      (node (ref "A05") (pin "V2") (pinfunction "P$2_V2") (pintype "bidirectional"))
      (node (ref "B05") (pin "V2") (pinfunction "P$2_V2") (pintype "bidirectional"))
      (node (ref "B19") (pin "R2") (pinfunction "OUT_R2") (pintype "output"))
    )
    (net (code "63") (name "I_EXTA1") (class "Default")
      (node (ref "A05") (pin "T2") (pinfunction "P$2_T2") (pintype "bidirectional"))
      (node (ref "B05") (pin "T2") (pinfunction "P$2_T2") (pintype "bidirectional"))
      (node (ref "B19") (pin "N2") (pinfunction "OUT_N2") (pintype "output"))
    )
    (net (code "64") (name "I_EXTA2") (class "Default")
      (node (ref "A05") (pin "S2") (pinfunction "P$2_S2") (pintype "bidirectional"))
      (node (ref "B05") (pin "S2") (pinfunction "P$2_S2") (pintype "bidirectional"))
      (node (ref "B19") (pin "L2") (pinfunction "OUT_L2") (pintype "output"))
    )
    (net (code "65") (name "I_INIT") (class "Default")
      (node (ref "A01") (pin "V2") (pinfunction "P$2_V2") (pintype "bidirectional"))
      (node (ref "A04") (pin "V2") (pinfunction "P$2_V2") (pintype "bidirectional"))
      (node (ref "B01") (pin "V2") (pinfunction "P$2_V2") (pintype "bidirectional"))
      (node (ref "B04") (pin "V2") (pinfunction "P$2_V2") (pintype "bidirectional"))
      (node (ref "B06") (pin "N1") (pinfunction "IN_N1") (pintype "input"))
    )
    (net (code "66") (name "I_IOP1") (class "Default")
      (node (ref "A01") (pin "K2") (pinfunction "P$2_K2") (pintype "bidirectional"))
      (node (ref "B01") (pin "K2") (pinfunction "P$2_K2") (pintype "bidirectional"))
      (node (ref "B06") (pin "A1") (pinfunction "IN1_A1") (pintype "input"))
    )
    (net (code "67") (name "I_IOP2") (class "Default")
      (node (ref "A01") (pin "M2") (pinfunction "P$2_M2") (pintype "bidirectional"))
      (node (ref "B01") (pin "M2") (pinfunction "P$2_M2") (pintype "bidirectional"))
      (node (ref "B06") (pin "D1") (pinfunction "IN_D1") (pintype "input"))
    )
    (net (code "68") (name "I_IOP4") (class "Default")
      (node (ref "A01") (pin "P2") (pinfunction "P$2_P2") (pintype "bidirectional"))
      (node (ref "B01") (pin "P2") (pinfunction "P$2_P2") (pintype "bidirectional"))
      (node (ref "B06") (pin "F1") (pinfunction "IN_F1") (pintype "input"))
    )
    (net (code "69") (name "I_IRQ") (class "Default")
      (node (ref "A03") (pin "M2") (pinfunction "P$2_M2") (pintype "bidirectional"))
      (node (ref "B03") (pin "M2") (pinfunction "P$2_M2") (pintype "bidirectional"))
      (node (ref "B18") (pin "F2") (pinfunction "OUT_F2") (pintype "output"))
    )
    (net (code "70") (name "I_LINE") (class "Default")
      (node (ref "A03") (pin "V2") (pinfunction "P$2_V2") (pintype "bidirectional"))
      (node (ref "B03") (pin "V2") (pinfunction "P$2_V2") (pintype "bidirectional"))
      (node (ref "B18") (pin "L2") (pinfunction "OUT_L2") (pintype "output"))
    )
    (net (code "71") (name "I_MB00") (class "Default")
      (node (ref "A02") (pin "B1") (pinfunction "P$2_B1") (pintype "bidirectional"))
      (node (ref "A06") (pin "B1") (pinfunction "CATHODE_B1") (pintype "passive"))
      (node (ref "A07") (pin "H2") (pinfunction "IN2_H2") (pintype "input"))
      (node (ref "B02") (pin "B1") (pinfunction "P$2_B1") (pintype "bidirectional"))
    )
    (net (code "72") (name "I_MB01") (class "Default")
      (node (ref "A02") (pin "D1") (pinfunction "P$2_D1") (pintype "bidirectional"))
      (node (ref "A06") (pin "D1") (pinfunction "CATHODE_D1") (pintype "passive"))
      (node (ref "A07") (pin "N2") (pinfunction "IN2_N2") (pintype "input"))
      (node (ref "B02") (pin "D1") (pinfunction "P$2_D1") (pintype "bidirectional"))
    )
    (net (code "73") (name "I_MB02") (class "Default")
      (node (ref "A02") (pin "E1") (pinfunction "P$2_E1") (pintype "bidirectional"))
      (node (ref "A06") (pin "E1") (pinfunction "CATHODE_E1") (pintype "passive"))
      (node (ref "A07") (pin "U2") (pinfunction "IN2_U2") (pintype "input"))
      (node (ref "B02") (pin "E1") (pinfunction "P$2_E1") (pintype "bidirectional"))
    )
    (net (code "74") (name "I_MB03") (class "Default")
      (node (ref "A02") (pin "J1") (pinfunction "P$2_J1") (pintype "bidirectional"))
      (node (ref "A06") (pin "J1") (pinfunction "CATHODE_J1") (pintype "passive"))
      (node (ref "A08") (pin "N2") (pinfunction "IN2_N2") (pintype "input"))
      (node (ref "B02") (pin "J1") (pinfunction "P$2_J1") (pintype "bidirectional"))
    )
    (net (code "75") (name "I_MB04") (class "Default")
      (node (ref "A02") (pin "M1") (pinfunction "P$2_M1") (pintype "bidirectional"))
      (node (ref "A06") (pin "M1") (pinfunction "CATHODE_M1") (pintype "passive"))
      (node (ref "A09") (pin "H2") (pinfunction "IN2_H2") (pintype "input"))
      (node (ref "B02") (pin "M1") (pinfunction "P$2_M1") (pintype "bidirectional"))
    )
    (net (code "76") (name "I_MB05") (class "Default")
      (node (ref "A02") (pin "S1") (pinfunction "P$2_S1") (pintype "bidirectional"))
      (node (ref "A06") (pin "S1") (pinfunction "CATHODE_S1") (pintype "passive"))
      (node (ref "A09") (pin "U2") (pinfunction "IN2_U2") (pintype "input"))
      (node (ref "B02") (pin "S1") (pinfunction "P$2_S1") (pintype "bidirectional"))
    )
    (net (code "77") (name "I_MB06") (class "Default")
      (node (ref "A02") (pin "E2") (pinfunction "P$2_E2") (pintype "bidirectional"))
      (node (ref "A06") (pin "E2") (pinfunction "CATHODE_E2") (pintype "passive"))
      (node (ref "A10") (pin "N2") (pinfunction "IN2_N2") (pintype "input"))
      (node (ref "B02") (pin "E2") (pinfunction "P$2_E2") (pintype "bidirectional"))
    )
    (net (code "78") (name "I_MB07") (class "Default")
      (node (ref "A02") (pin "K2") (pinfunction "P$2_K2") (pintype "bidirectional"))
      (node (ref "A06") (pin "K2") (pinfunction "CATHODE_K2") (pintype "passive"))
      (node (ref "A11") (pin "H2") (pinfunction "IN2_H2") (pintype "input"))
      (node (ref "B02") (pin "K2") (pinfunction "P$2_K2") (pintype "bidirectional"))
    )
    (net (code "79") (name "I_MB08") (class "Default")
      (node (ref "A02") (pin "P2") (pinfunction "P$2_P2") (pintype "bidirectional"))
      (node (ref "A06") (pin "P2") (pinfunction "CATHODE_P2") (pintype "passive"))
      (node (ref "A11") (pin "U2") (pinfunction "IN2_U2") (pintype "input"))
      (node (ref "B02") (pin "P2") (pinfunction "P$2_P2") (pintype "bidirectional"))
    )
    (net (code "80") (name "I_MB09") (class "Default")
      (node (ref "A02") (pin "S2") (pinfunction "P$2_S2") (pintype "bidirectional"))
      (node (ref "A06") (pin "S2") (pinfunction "CATHODE_S2") (pintype "passive"))
      (node (ref "A12") (pin "H2") (pinfunction "IN2_H2") (pintype "input"))
      (node (ref "B02") (pin "S2") (pinfunction "P$2_S2") (pintype "bidirectional"))
    )
    (net (code "81") (name "I_MB10") (class "Default")
      (node (ref "A02") (pin "T2") (pinfunction "P$2_T2") (pintype "bidirectional"))
      (node (ref "A06") (pin "T2") (pinfunction "CATHODE_T2") (pintype "passive"))
      (node (ref "A12") (pin "N2") (pinfunction "IN2_N2") (pintype "input"))
      (node (ref "B02") (pin "T2") (pinfunction "P$2_T2") (pintype "bidirectional"))
    )
    (net (code "82") (name "I_MB11") (class "Default")
      (node (ref "A02") (pin "V2") (pinfunction "P$2_V2") (pintype "bidirectional"))
      (node (ref "A06") (pin "V2") (pinfunction "CATHODE_V2") (pintype "passive"))
      (node (ref "A12") (pin "U2") (pinfunction "IN2_U2") (pintype "input"))
      (node (ref "B02") (pin "V2") (pinfunction "P$2_V2") (pintype "bidirectional"))
    )
    (net (code "83") (name "I_MBINCR") (class "Default")
      (node (ref "A04") (pin "T2") (pinfunction "P$2_T2") (pintype "bidirectional"))
      (node (ref "B04") (pin "T2") (pinfunction "P$2_T2") (pintype "bidirectional"))
      (node (ref "B19") (pin "D2") (pinfunction "OUT_D2") (pintype "output"))
    )
    (net (code "84") (name "I_RUN") (class "Default")
      (node (ref "A03") (pin "S2") (pinfunction "P$2_S2") (pintype "bidirectional"))
      (node (ref "B03") (pin "S2") (pinfunction "P$2_S2") (pintype "bidirectional"))
      (node (ref "B07") (pin "K2") (pinfunction "CATHODE_K2") (pintype "passive"))
      (node (ref "B14") (pin "H2") (pinfunction "IN2_H2") (pintype "input"))
    )
    (net (code "85") (name "I_SKIP") (class "Default")
      (node (ref "A03") (pin "K2") (pinfunction "P$2_K2") (pintype "bidirectional"))
      (node (ref "B03") (pin "K2") (pinfunction "P$2_K2") (pintype "bidirectional"))
      (node (ref "B18") (pin "D2") (pinfunction "OUT_D2") (pintype "output"))
    )
    (net (code "86") (name "I_TS1") (class "Default")
      (node (ref "A01") (pin "T2") (pinfunction "P$2_T2") (pintype "bidirectional"))
      (node (ref "B01") (pin "T2") (pinfunction "P$2_T2") (pintype "bidirectional"))
      (node (ref "B06") (pin "L1") (pinfunction "IN_L1") (pintype "input"))
    )
    (net (code "87") (name "I_TS3") (class "Default")
      (node (ref "A01") (pin "S2") (pinfunction "P$2_S2") (pintype "bidirectional"))
      (node (ref "B01") (pin "S2") (pinfunction "P$2_S2") (pintype "bidirectional"))
      (node (ref "B06") (pin "J1") (pinfunction "IN_J1") (pintype "input"))
    )
    (net (code "88") (name "I_TT_INST") (class "Default")
      (node (ref "A03") (pin "T2") (pinfunction "P$2_T2") (pintype "bidirectional"))
      (node (ref "B03") (pin "T2") (pinfunction "P$2_T2") (pintype "bidirectional"))
      (node (ref "B07") (pin "M2") (pinfunction "CATHODE_M2") (pintype "passive"))
      (node (ref "B14") (pin "N2") (pinfunction "IN2_N2") (pintype "input"))
    )
    (net (code "89") (name "I_WCOV") (class "Default")
      (node (ref "A05") (pin "P2") (pinfunction "P$2_P2") (pintype "bidirectional"))
      (node (ref "B05") (pin "P2") (pinfunction "P$2_P2") (pintype "bidirectional"))
      (node (ref "B07") (pin "T2") (pinfunction "CATHODE_T2") (pintype "passive"))
      (node (ref "B15") (pin "N2") (pinfunction "IN2_N2") (pintype "input"))
    )
    (net (code "90") (name "Net-(B06A-OUT)") (class "Default")
      (node (ref "B06") (pin "B1") (pinfunction "OUT_B1") (pintype "output"))
      (node (ref "B08") (pin "H2") (pinfunction "IN2_H2") (pintype "input"))
    )
    (net (code "91") (name "Net-(B06B-OUT)") (class "Default")
      (node (ref "B06") (pin "E1") (pinfunction "OUT_E1") (pintype "output"))
      (node (ref "B08") (pin "N2") (pinfunction "IN2_N2") (pintype "input"))
    )
    (net (code "92") (name "Net-(B06F-OUT)") (class "Default")
      (node (ref "B06") (pin "H1") (pinfunction "OUT_H1") (pintype "output"))
      (node (ref "B08") (pin "U2") (pinfunction "IN2_U2") (pintype "input"))
    )
    (net (code "93") (name "Net-(B06H-OUT)") (class "Default")
      (node (ref "B06") (pin "K1") (pinfunction "OUT_K1") (pintype "output"))
      (node (ref "B09") (pin "H2") (pinfunction "IN2_H2") (pintype "input"))
    )
    (net (code "94") (name "Net-(B06J-OUT)") (class "Default")
      (node (ref "B06") (pin "M1") (pinfunction "OUT_M1") (pintype "output"))
      (node (ref "B09") (pin "N2") (pinfunction "IN2_N2") (pintype "input"))
    )
    (net (code "95") (name "Net-(B06L-OUT)") (class "Default")
      (node (ref "B06") (pin "P1") (pinfunction "OUT_P1") (pintype "output"))
      (node (ref "B09") (pin "U2") (pinfunction "IN2_U2") (pintype "input"))
    )
    (net (code "96") (name "O_3CYCLE") (class "Default")
      (node (ref "A22") (pin "K2") (pinfunction "P$2_K2") (pintype "bidirectional"))
      (node (ref "B19") (pin "H2") (pinfunction "IN_H2") (pintype "input"))
    )
    (net (code "97") (name "O_AC00") (class "Default")
      (node (ref "A17") (pin "D2") (pinfunction "P$2_D2") (pintype "bidirectional"))
      (node (ref "B16") (pin "E2") (pinfunction "IN_E2") (pintype "input"))
    )
    (net (code "98") (name "O_AC01") (class "Default")
      (node (ref "A17") (pin "E2") (pinfunction "P$2_E2") (pintype "bidirectional"))
      (node (ref "B16") (pin "H2") (pinfunction "IN_H2") (pintype "input"))
    )
    (net (code "99") (name "O_AC02") (class "Default")
      (node (ref "A17") (pin "H2") (pinfunction "P$2_H2") (pintype "bidirectional"))
      (node (ref "B16") (pin "K2") (pinfunction "IN_K2") (pintype "input"))
    )
    (net (code "100") (name "O_AC03") (class "Default")
      (node (ref "A17") (pin "K2") (pinfunction "P$2_K2") (pintype "bidirectional"))
      (node (ref "B16") (pin "M2") (pinfunction "IN_M2") (pintype "input"))
    )
    (net (code "101") (name "O_AC04") (class "Default")
      (node (ref "A17") (pin "M2") (pinfunction "P$2_M2") (pintype "bidirectional"))
      (node (ref "B16") (pin "P2") (pinfunction "IN_P2") (pintype "input"))
    )
    (net (code "102") (name "O_AC05") (class "Default")
      (node (ref "A17") (pin "P2") (pinfunction "P$2_P2") (pintype "bidirectional"))
      (node (ref "B16") (pin "S2") (pinfunction "IN_S2") (pintype "input"))
    )
    (net (code "103") (name "O_AC06") (class "Default")
      (node (ref "A17") (pin "S2") (pinfunction "P$2_S2") (pintype "bidirectional"))
      (node (ref "B17") (pin "E2") (pinfunction "IN_E2") (pintype "input"))
    )
    (net (code "104") (name "O_AC07") (class "Default")
      (node (ref "A17") (pin "T2") (pinfunction "P$2_T2") (pintype "bidirectional"))
      (node (ref "B17") (pin "H2") (pinfunction "IN_H2") (pintype "input"))
    )
    (net (code "105") (name "O_AC08") (class "Default")
      (node (ref "A17") (pin "V2") (pinfunction "P$2_V2") (pintype "bidirectional"))
      (node (ref "B17") (pin "K2") (pinfunction "IN_K2") (pintype "input"))
    )
    (net (code "106") (name "O_AC09") (class "Default")
      (node (ref "A18") (pin "D2") (pinfunction "P$2_D2") (pintype "bidirectional"))
      (node (ref "B17") (pin "M2") (pinfunction "IN_M2") (pintype "input"))
    )
    (net (code "107") (name "O_AC10") (class "Default")
      (node (ref "A18") (pin "E2") (pinfunction "P$2_E2") (pintype "bidirectional"))
      (node (ref "B17") (pin "P2") (pinfunction "IN_P2") (pintype "input"))
    )
    (net (code "108") (name "O_AC11") (class "Default")
      (node (ref "A18") (pin "H2") (pinfunction "P$2_H2") (pintype "bidirectional"))
      (node (ref "B17") (pin "S2") (pinfunction "IN_S2") (pintype "input"))
    )
    (net (code "109") (name "O_ACCEPT") (class "Default")
      (node (ref "A20") (pin "S2") (pinfunction "P$2_S2") (pintype "bidirectional"))
      (node (ref "B15") (pin "D2") (pinfunction "OUT_D2") (pintype "output"))
    )
    (net (code "110") (name "O_ACCLR") (class "Default")
      (node (ref "A18") (pin "P2") (pinfunction "P$2_P2") (pintype "bidirectional"))
      (node (ref "B18") (pin "K2") (pinfunction "IN_K2") (pintype "input"))
    )
    (net (code "111") (name "O_ADD00") (class "Default")
      (node (ref "A19") (pin "D2") (pinfunction "P$2_D2") (pintype "bidirectional"))
      (node (ref "B20") (pin "E2") (pinfunction "IN_E2") (pintype "input"))
    )
    (net (code "112") (name "O_ADD01") (class "Default")
      (node (ref "A19") (pin "E2") (pinfunction "P$2_E2") (pintype "bidirectional"))
      (node (ref "B20") (pin "H2") (pinfunction "IN_H2") (pintype "input"))
    )
    (net (code "113") (name "O_ADD02") (class "Default")
      (node (ref "A19") (pin "H2") (pinfunction "P$2_H2") (pintype "bidirectional"))
      (node (ref "B20") (pin "K2") (pinfunction "IN_K2") (pintype "input"))
    )
    (net (code "114") (name "O_ADD03") (class "Default")
      (node (ref "A19") (pin "K2") (pinfunction "P$2_K2") (pintype "bidirectional"))
      (node (ref "B20") (pin "M2") (pinfunction "IN_M2") (pintype "input"))
    )
    (net (code "115") (name "O_ADD04") (class "Default")
      (node (ref "A19") (pin "M2") (pinfunction "P$2_M2") (pintype "bidirectional"))
      (node (ref "B20") (pin "P2") (pinfunction "IN_P2") (pintype "input"))
    )
    (net (code "116") (name "O_ADD05") (class "Default")
      (node (ref "A19") (pin "P2") (pinfunction "P$2_P2") (pintype "bidirectional"))
      (node (ref "B20") (pin "S2") (pinfunction "IN_S2") (pintype "input"))
    )
    (net (code "117") (name "O_ADD06") (class "Default")
      (node (ref "A19") (pin "S2") (pinfunction "P$2_S2") (pintype "bidirectional"))
      (node (ref "B21A") (pin "E2") (pinfunction "IN_E2") (pintype "input"))
    )
    (net (code "118") (name "O_ADD07") (class "Default")
      (node (ref "A19") (pin "T2") (pinfunction "P$2_T2") (pintype "bidirectional"))
      (node (ref "B21A") (pin "H2") (pinfunction "IN_H2") (pintype "input"))
    )
    (net (code "119") (name "O_ADD08") (class "Default")
      (node (ref "A19") (pin "V2") (pinfunction "P$2_V2") (pintype "bidirectional"))
      (node (ref "B21A") (pin "K2") (pinfunction "IN_K2") (pintype "input"))
    )
    (net (code "120") (name "O_ADD09") (class "Default")
      (node (ref "A20") (pin "D2") (pinfunction "P$2_D2") (pintype "bidirectional"))
      (node (ref "B21A") (pin "M2") (pinfunction "IN_M2") (pintype "input"))
    )
    (net (code "121") (name "O_ADD10") (class "Default")
      (node (ref "A20") (pin "E2") (pinfunction "P$2_E2") (pintype "bidirectional"))
      (node (ref "B21A") (pin "P2") (pinfunction "IN_P2") (pintype "input"))
    )
    (net (code "122") (name "O_ADD11") (class "Default")
      (node (ref "A20") (pin "H2") (pinfunction "P$2_H2") (pintype "bidirectional"))
      (node (ref "B21A") (pin "S2") (pinfunction "IN_S2") (pintype "input"))
    )
    (net (code "123") (name "O_BAC00") (class "Default")
      (node (ref "A13") (pin "D2") (pinfunction "P$2_D2") (pintype "bidirectional"))
      (node (ref "B10") (pin "D2") (pinfunction "OUT_D2") (pintype "output"))
    )
    (net (code "124") (name "O_BAC01") (class "Default")
      (node (ref "A13") (pin "E2") (pinfunction "P$2_E2") (pintype "bidirectional"))
      (node (ref "B10") (pin "K2") (pinfunction "OUT_K2") (pintype "output"))
    )
    (net (code "125") (name "O_BAC02") (class "Default")
      (node (ref "A13") (pin "H2") (pinfunction "P$2_H2") (pintype "bidirectional"))
      (node (ref "B10") (pin "S2") (pinfunction "OUT_S2") (pintype "output"))
    )
    (net (code "126") (name "O_BAC03") (class "Default")
      (node (ref "A13") (pin "K2") (pinfunction "P$2_K2") (pintype "bidirectional"))
      (node (ref "B11") (pin "D2") (pinfunction "OUT_D2") (pintype "output"))
    )
    (net (code "127") (name "O_BAC04") (class "Default")
      (node (ref "A13") (pin "M2") (pinfunction "P$2_M2") (pintype "bidirectional"))
      (node (ref "B11") (pin "K2") (pinfunction "OUT_K2") (pintype "output"))
    )
    (net (code "128") (name "O_BAC05") (class "Default")
      (node (ref "A13") (pin "P2") (pinfunction "P$2_P2") (pintype "bidirectional"))
      (node (ref "B11") (pin "S2") (pinfunction "OUT_S2") (pintype "output"))
    )
    (net (code "129") (name "O_BAC06") (class "Default")
      (node (ref "A13") (pin "S2") (pinfunction "P$2_S2") (pintype "bidirectional"))
      (node (ref "B12") (pin "D2") (pinfunction "OUT_D2") (pintype "output"))
    )
    (net (code "130") (name "O_BAC07") (class "Default")
      (node (ref "A13") (pin "T2") (pinfunction "P$2_T2") (pintype "bidirectional"))
      (node (ref "B12") (pin "K2") (pinfunction "OUT_K2") (pintype "output"))
    )
    (net (code "131") (name "O_BAC08") (class "Default")
      (node (ref "A13") (pin "V2") (pinfunction "P$2_V2") (pintype "bidirectional"))
      (node (ref "B12") (pin "S2") (pinfunction "OUT_S2") (pintype "output"))
    )
    (net (code "132") (name "O_BAC09") (class "Default")
      (node (ref "A14") (pin "D2") (pinfunction "P$2_D2") (pintype "bidirectional"))
      (node (ref "B13") (pin "D2") (pinfunction "OUT_D2") (pintype "output"))
    )
    (net (code "133") (name "O_BAC10") (class "Default")
      (node (ref "A14") (pin "E2") (pinfunction "P$2_E2") (pintype "bidirectional"))
      (node (ref "B13") (pin "K2") (pinfunction "OUT_K2") (pintype "output"))
    )
    (net (code "134") (name "O_BAC11") (class "Default")
      (node (ref "A14") (pin "H2") (pinfunction "P$2_H2") (pintype "bidirectional"))
      (node (ref "B13") (pin "S2") (pinfunction "OUT_S2") (pintype "output"))
    )
    (net (code "135") (name "O_BREAK") (class "Default")
      (node (ref "A20") (pin "P2") (pinfunction "P$2_P2") (pintype "bidirectional"))
      (node (ref "B14") (pin "S2") (pinfunction "OUT_S2") (pintype "output"))
    )
    (net (code "136") (name "O_BRKRQ") (class "Default")
      (node (ref "A20") (pin "K2") (pinfunction "P$2_K2") (pintype "bidirectional"))
      (node (ref "B18") (pin "P2") (pinfunction "IN_P2") (pintype "input"))
    )
    (net (code "137") (name "O_CAINCR") (class "Default")
      (node (ref "A22") (pin "M2") (pinfunction "P$2_M2") (pintype "bidirectional"))
      (node (ref "B19") (pin "K2") (pinfunction "IN_K2") (pintype "input"))
    )
    (net (code "138") (name "O_DATA00") (class "Default")
      (node (ref "A21") (pin "D2") (pinfunction "P$2_D2") (pintype "bidirectional"))
      (node (ref "B22") (pin "E2") (pinfunction "IN_E2") (pintype "input"))
    )
    (net (code "139") (name "O_DATA01") (class "Default")
      (node (ref "A21") (pin "E2") (pinfunction "P$2_E2") (pintype "bidirectional"))
      (node (ref "B22") (pin "H2") (pinfunction "IN_H2") (pintype "input"))
    )
    (net (code "140") (name "O_DATA02") (class "Default")
      (node (ref "A21") (pin "H2") (pinfunction "P$2_H2") (pintype "bidirectional"))
      (node (ref "B22") (pin "K2") (pinfunction "IN_K2") (pintype "input"))
    )
    (net (code "141") (name "O_DATA03") (class "Default")
      (node (ref "A21") (pin "K2") (pinfunction "P$2_K2") (pintype "bidirectional"))
      (node (ref "B22") (pin "M2") (pinfunction "IN_M2") (pintype "input"))
    )
    (net (code "142") (name "O_DATA04") (class "Default")
      (node (ref "A21") (pin "M2") (pinfunction "P$2_M2") (pintype "bidirectional"))
      (node (ref "B22") (pin "P2") (pinfunction "IN_P2") (pintype "input"))
    )
    (net (code "143") (name "O_DATA05") (class "Default")
      (node (ref "A21") (pin "P2") (pinfunction "P$2_P2") (pintype "bidirectional"))
      (node (ref "B22") (pin "S2") (pinfunction "IN_S2") (pintype "input"))
    )
    (net (code "144") (name "O_DATA06") (class "Default")
      (node (ref "A21") (pin "S2") (pinfunction "P$2_S2") (pintype "bidirectional"))
      (node (ref "B23") (pin "E2") (pinfunction "IN_E2") (pintype "input"))
    )
    (net (code "145") (name "O_DATA07") (class "Default")
      (node (ref "A21") (pin "T2") (pinfunction "P$2_T2") (pintype "bidirectional"))
      (node (ref "B23") (pin "H2") (pinfunction "IN_H2") (pintype "input"))
    )
    (net (code "146") (name "O_DATA08") (class "Default")
      (node (ref "A21") (pin "V2") (pinfunction "P$2_V2") (pintype "bidirectional"))
      (node (ref "B23") (pin "K2") (pinfunction "IN_K2") (pintype "input"))
    )
    (net (code "147") (name "O_DATA09") (class "Default")
      (node (ref "A22") (pin "D2") (pinfunction "P$2_D2") (pintype "bidirectional"))
      (node (ref "B23") (pin "M2") (pinfunction "IN_M2") (pintype "input"))
    )
    (net (code "148") (name "O_DATA10") (class "Default")
      (node (ref "A22") (pin "E2") (pinfunction "P$2_E2") (pintype "bidirectional"))
      (node (ref "B23") (pin "P2") (pinfunction "IN_P2") (pintype "input"))
    )
    (net (code "149") (name "O_DATA11") (class "Default")
      (node (ref "A22") (pin "H2") (pinfunction "P$2_H2") (pintype "bidirectional"))
      (node (ref "B23") (pin "S2") (pinfunction "IN_S2") (pintype "input"))
    )
    (net (code "150") (name "O_DATAIN") (class "Default")
      (node (ref "A20") (pin "M2") (pinfunction "P$2_M2") (pintype "bidirectional"))
      (node (ref "B18") (pin "S2") (pinfunction "IN_S2") (pintype "input"))
    )
    (net (code "151") (name "O_EXTA0") (class "Default")
      (node (ref "A23") (pin "H2") (pinfunction "P$2_H2") (pintype "bidirectional"))
      (node (ref "B19") (pin "S2") (pinfunction "IN_S2") (pintype "input"))
    )
    (net (code "152") (name "O_EXTA1") (class "Default")
      (node (ref "A23") (pin "E2") (pinfunction "P$2_E2") (pintype "bidirectional"))
      (node (ref "B19") (pin "P2") (pinfunction "IN_P2") (pintype "input"))
    )
    (net (code "153") (name "O_EXTA2") (class "Default")
      (node (ref "A23") (pin "D2") (pinfunction "P$2_D2") (pintype "bidirectional"))
      (node (ref "B19") (pin "M2") (pinfunction "IN_M2") (pintype "input"))
    )
    (net (code "154") (name "O_INIT") (class "Default")
      (node (ref "A14") (pin "V2") (pinfunction "P$2_V2") (pintype "bidirectional"))
      (node (ref "B09") (pin "S2") (pinfunction "OUT_S2") (pintype "output"))
    )
    (net (code "155") (name "O_IOP1") (class "Default")
      (node (ref "A14") (pin "K2") (pinfunction "P$2_K2") (pintype "bidirectional"))
      (node (ref "B08") (pin "D2") (pinfunction "OUT_D2") (pintype "output"))
    )
    (net (code "156") (name "O_IOP2") (class "Default")
      (node (ref "A14") (pin "M2") (pinfunction "P$2_M2") (pintype "bidirectional"))
      (node (ref "B08") (pin "K2") (pinfunction "OUT_K2") (pintype "output"))
    )
    (net (code "157") (name "O_IOP4") (class "Default")
      (node (ref "A14") (pin "P2") (pinfunction "P$2_P2") (pintype "bidirectional"))
      (node (ref "B08") (pin "S2") (pinfunction "OUT_S2") (pintype "output"))
    )
    (net (code "158") (name "O_IRQ") (class "Default")
      (node (ref "A18") (pin "M2") (pinfunction "P$2_M2") (pintype "bidirectional"))
      (node (ref "B18") (pin "H2") (pinfunction "IN_H2") (pintype "input"))
    )
    (net (code "159") (name "O_LINE") (class "Default")
      (node (ref "A18") (pin "V2") (pinfunction "P$2_V2") (pintype "bidirectional"))
      (node (ref "B18") (pin "M2") (pinfunction "IN_M2") (pintype "input"))
    )
    (net (code "160") (name "O_MB00") (class "Default")
      (node (ref "A07") (pin "D2") (pinfunction "OUT_D2") (pintype "output"))
      (node (ref "A15") (pin "D2") (pinfunction "P$2_D2") (pintype "bidirectional"))
    )
    (net (code "161") (name "O_MB01") (class "Default")
      (node (ref "A07") (pin "K2") (pinfunction "OUT_K2") (pintype "output"))
      (node (ref "A15") (pin "E2") (pinfunction "P$2_E2") (pintype "bidirectional"))
    )
    (net (code "162") (name "O_MB02") (class "Default")
      (node (ref "A07") (pin "S2") (pinfunction "OUT_S2") (pintype "output"))
      (node (ref "A15") (pin "H2") (pinfunction "P$2_H2") (pintype "bidirectional"))
    )
    (net (code "163") (name "O_MB03") (class "Default")
      (node (ref "A08") (pin "K2") (pinfunction "OUT_K2") (pintype "output"))
      (node (ref "A15") (pin "M2") (pinfunction "P$2_M2") (pintype "bidirectional"))
    )
    (net (code "164") (name "O_MB04") (class "Default")
      (node (ref "A09") (pin "D2") (pinfunction "OUT_D2") (pintype "output"))
      (node (ref "A15") (pin "S2") (pinfunction "P$2_S2") (pintype "bidirectional"))
    )
    (net (code "165") (name "O_MB05") (class "Default")
      (node (ref "A09") (pin "S2") (pinfunction "OUT_S2") (pintype "output"))
      (node (ref "A15") (pin "V2") (pinfunction "P$2_V2") (pintype "bidirectional"))
    )
    (net (code "166") (name "O_MB06") (class "Default")
      (node (ref "A10") (pin "K2") (pinfunction "OUT_K2") (pintype "output"))
      (node (ref "A16") (pin "E2") (pinfunction "P$2_E2") (pintype "bidirectional"))
    )
    (net (code "167") (name "O_MB07") (class "Default")
      (node (ref "A11") (pin "D2") (pinfunction "OUT_D2") (pintype "output"))
      (node (ref "A16") (pin "K2") (pinfunction "P$2_K2") (pintype "bidirectional"))
    )
    (net (code "168") (name "O_MB08") (class "Default")
      (node (ref "A11") (pin "S2") (pinfunction "OUT_S2") (pintype "output"))
      (node (ref "A16") (pin "P2") (pinfunction "P$2_P2") (pintype "bidirectional"))
    )
    (net (code "169") (name "O_MB09") (class "Default")
      (node (ref "A12") (pin "D2") (pinfunction "OUT_D2") (pintype "output"))
      (node (ref "A16") (pin "S2") (pinfunction "P$2_S2") (pintype "bidirectional"))
    )
    (net (code "170") (name "O_MB10") (class "Default")
      (node (ref "A12") (pin "K2") (pinfunction "OUT_K2") (pintype "output"))
      (node (ref "A16") (pin "T2") (pinfunction "P$2_T2") (pintype "bidirectional"))
    )
    (net (code "171") (name "O_MB11") (class "Default")
      (node (ref "A12") (pin "S2") (pinfunction "OUT_S2") (pintype "output"))
      (node (ref "A16") (pin "V2") (pinfunction "P$2_V2") (pintype "bidirectional"))
    )
    (net (code "172") (name "O_MBINCR") (class "Default")
      (node (ref "A20") (pin "T2") (pinfunction "P$2_T2") (pintype "bidirectional"))
      (node (ref "B19") (pin "E2") (pinfunction "IN_E2") (pintype "input"))
    )
    (net (code "173") (name "O_RUN") (class "Default")
      (node (ref "A18") (pin "S2") (pinfunction "P$2_S2") (pintype "bidirectional"))
      (node (ref "B14") (pin "D2") (pinfunction "OUT_D2") (pintype "output"))
    )
    (net (code "174") (name "O_SKIP") (class "Default")
      (node (ref "A18") (pin "K2") (pinfunction "P$2_K2") (pintype "bidirectional"))
      (node (ref "B18") (pin "E2") (pinfunction "IN_E2") (pintype "input"))
    )
    (net (code "175") (name "O_TS1") (class "Default")
      (node (ref "A14") (pin "T2") (pinfunction "P$2_T2") (pintype "bidirectional"))
      (node (ref "B09") (pin "K2") (pinfunction "OUT_K2") (pintype "output"))
    )
    (net (code "176") (name "O_TS3") (class "Default")
      (node (ref "A14") (pin "S2") (pinfunction "P$2_S2") (pintype "bidirectional"))
      (node (ref "B09") (pin "D2") (pinfunction "OUT_D2") (pintype "output"))
    )
    (net (code "177") (name "O_TT_INST") (class "Default")
      (node (ref "A18") (pin "T2") (pinfunction "P$2_T2") (pintype "bidirectional"))
      (node (ref "B14") (pin "K2") (pinfunction "OUT_K2") (pintype "output"))
    )
    (net (code "178") (name "O_WCOV") (class "Default")
      (node (ref "A22") (pin "P2") (pinfunction "P$2_P2") (pintype "bidirectional"))
      (node (ref "B15") (pin "K2") (pinfunction "OUT_K2") (pintype "output"))
    )
    (net (code "180") (name "unconnected-(A07A-SLOW-PadE2)") (class "Default")
      (node (ref "A07") (pin "E2") (pinfunction "SLOW_E2") (pintype "passive"))
    )
    (net (code "181") (name "unconnected-(A07D-SLOW-PadL2)") (class "Default")
      (node (ref "A07") (pin "L2") (pinfunction "SLOW_L2") (pintype "passive"))
    )
    (net (code "182") (name "unconnected-(A07E-SLOW-PadR2)") (class "Default")
      (node (ref "A07") (pin "R2") (pinfunction "SLOW_R2") (pintype "passive"))
    )
    (net (code "183") (name "unconnected-(A08A-SLOW-PadE2)") (class "Default")
      (node (ref "A08") (pin "E2") (pinfunction "SLOW_E2") (pintype "passive"))
    )
    (net (code "184") (name "unconnected-(A08D-SLOW-PadL2)") (class "Default")
      (node (ref "A08") (pin "L2") (pinfunction "SLOW_L2") (pintype "passive"))
    )
    (net (code "185") (name "unconnected-(A08E-SLOW-PadR2)") (class "Default")
      (node (ref "A08") (pin "R2") (pinfunction "SLOW_R2") (pintype "passive"))
    )
    (net (code "186") (name "unconnected-(A09A-SLOW-PadE2)") (class "Default")
      (node (ref "A09") (pin "E2") (pinfunction "SLOW_E2") (pintype "passive"))
    )
    (net (code "187") (name "unconnected-(A09D-SLOW-PadL2)") (class "Default")
      (node (ref "A09") (pin "L2") (pinfunction "SLOW_L2") (pintype "passive"))
    )
    (net (code "188") (name "unconnected-(A09E-SLOW-PadR2)") (class "Default")
      (node (ref "A09") (pin "R2") (pinfunction "SLOW_R2") (pintype "passive"))
    )
    (net (code "189") (name "unconnected-(A10A-SLOW-PadE2)") (class "Default")
      (node (ref "A10") (pin "E2") (pinfunction "SLOW_E2") (pintype "passive"))
    )
    (net (code "190") (name "unconnected-(A10D-SLOW-PadL2)") (class "Default")
      (node (ref "A10") (pin "L2") (pinfunction "SLOW_L2") (pintype "passive"))
    )
    (net (code "191") (name "unconnected-(A10E-SLOW-PadR2)") (class "Default")
      (node (ref "A10") (pin "R2") (pinfunction "SLOW_R2") (pintype "passive"))
    )
    (net (code "192") (name "unconnected-(A11A-SLOW-PadE2)") (class "Default")
      (node (ref "A11") (pin "E2") (pinfunction "SLOW_E2") (pintype "passive"))
    )
    (net (code "193") (name "unconnected-(A11D-SLOW-PadL2)") (class "Default")
      (node (ref "A11") (pin "L2") (pinfunction "SLOW_L2") (pintype "passive"))
    )
    (net (code "194") (name "unconnected-(A11E-SLOW-PadR2)") (class "Default")
      (node (ref "A11") (pin "R2") (pinfunction "SLOW_R2") (pintype "passive"))
    )
    (net (code "195") (name "unconnected-(A12A-SLOW-PadE2)") (class "Default")
      (node (ref "A12") (pin "E2") (pinfunction "SLOW_E2") (pintype "passive"))
    )
    (net (code "196") (name "unconnected-(A12D-SLOW-PadL2)") (class "Default")
      (node (ref "A12") (pin "L2") (pinfunction "SLOW_L2") (pintype "passive"))
    )
    (net (code "197") (name "unconnected-(A12E-SLOW-PadR2)") (class "Default")
      (node (ref "A12") (pin "R2") (pinfunction "SLOW_R2") (pintype "passive"))
    )
    (net (code "198") (name "unconnected-(B08A-SLOW-PadE2)") (class "Default")
      (node (ref "B08") (pin "E2") (pinfunction "SLOW_E2") (pintype "passive"))
    )
    (net (code "199") (name "unconnected-(B08D-SLOW-PadL2)") (class "Default")
      (node (ref "B08") (pin "L2") (pinfunction "SLOW_L2") (pintype "passive"))
    )
    (net (code "200") (name "unconnected-(B08E-SLOW-PadR2)") (class "Default")
      (node (ref "B08") (pin "R2") (pinfunction "SLOW_R2") (pintype "passive"))
    )
    (net (code "201") (name "unconnected-(B09A-SLOW-PadE2)") (class "Default")
      (node (ref "B09") (pin "E2") (pinfunction "SLOW_E2") (pintype "passive"))
    )
    (net (code "202") (name "unconnected-(B09D-SLOW-PadL2)") (class "Default")
      (node (ref "B09") (pin "L2") (pinfunction "SLOW_L2") (pintype "passive"))
    )
    (net (code "203") (name "unconnected-(B09E-SLOW-PadR2)") (class "Default")
      (node (ref "B09") (pin "R2") (pinfunction "SLOW_R2") (pintype "passive"))
    )
    (net (code "204") (name "unconnected-(B10A-SLOW-PadE2)") (class "Default")
      (node (ref "B10") (pin "E2") (pinfunction "SLOW_E2") (pintype "passive"))
    )
    (net (code "205") (name "unconnected-(B10D-SLOW-PadL2)") (class "Default")
      (node (ref "B10") (pin "L2") (pinfunction "SLOW_L2") (pintype "passive"))
    )
    (net (code "206") (name "unconnected-(B10E-SLOW-PadR2)") (class "Default")
      (node (ref "B10") (pin "R2") (pinfunction "SLOW_R2") (pintype "passive"))
    )
    (net (code "207") (name "unconnected-(B11A-SLOW-PadE2)") (class "Default")
      (node (ref "B11") (pin "E2") (pinfunction "SLOW_E2") (pintype "passive"))
    )
    (net (code "208") (name "unconnected-(B11D-SLOW-PadL2)") (class "Default")
      (node (ref "B11") (pin "L2") (pinfunction "SLOW_L2") (pintype "passive"))
    )
    (net (code "209") (name "unconnected-(B11E-SLOW-PadR2)") (class "Default")
      (node (ref "B11") (pin "R2") (pinfunction "SLOW_R2") (pintype "passive"))
    )
    (net (code "210") (name "unconnected-(B12A-SLOW-PadE2)") (class "Default")
      (node (ref "B12") (pin "E2") (pinfunction "SLOW_E2") (pintype "passive"))
    )
    (net (code "211") (name "unconnected-(B12D-SLOW-PadL2)") (class "Default")
      (node (ref "B12") (pin "L2") (pinfunction "SLOW_L2") (pintype "passive"))
    )
    (net (code "212") (name "unconnected-(B12E-SLOW-PadR2)") (class "Default")
      (node (ref "B12") (pin "R2") (pinfunction "SLOW_R2") (pintype "passive"))
    )
    (net (code "213") (name "unconnected-(B13A-SLOW-PadE2)") (class "Default")
      (node (ref "B13") (pin "E2") (pinfunction "SLOW_E2") (pintype "passive"))
    )
    (net (code "214") (name "unconnected-(B13D-SLOW-PadL2)") (class "Default")
      (node (ref "B13") (pin "L2") (pinfunction "SLOW_L2") (pintype "passive"))
    )
    (net (code "215") (name "unconnected-(B13E-SLOW-PadR2)") (class "Default")
      (node (ref "B13") (pin "R2") (pinfunction "SLOW_R2") (pintype "passive"))
    )
    (net (code "216") (name "unconnected-(B14A-SLOW-PadE2)") (class "Default")
      (node (ref "B14") (pin "E2") (pinfunction "SLOW_E2") (pintype "passive"))
    )
    (net (code "217") (name "unconnected-(B14D-SLOW-PadL2)") (class "Default")
      (node (ref "B14") (pin "L2") (pinfunction "SLOW_L2") (pintype "passive"))
    )
    (net (code "218") (name "unconnected-(B14E-SLOW-PadR2)") (class "Default")
      (node (ref "B14") (pin "R2") (pinfunction "SLOW_R2") (pintype "passive"))
    )
    (net (code "219") (name "unconnected-(B15A-SLOW-PadE2)") (class "Default")
      (node (ref "B15") (pin "E2") (pinfunction "SLOW_E2") (pintype "passive"))
    )
    (net (code "220") (name "unconnected-(B15D-SLOW-PadL2)") (class "Default")
      (node (ref "B15") (pin "L2") (pinfunction "SLOW_L2") (pintype "passive"))
    )
    (net (code "221") (name "~{I_MB03}") (class "Default")
      (node (ref "A02") (pin "H1") (pinfunction "P$2_H1") (pintype "bidirectional"))
      (node (ref "A06") (pin "H1") (pinfunction "CATHODE_H1") (pintype "passive"))
      (node (ref "A08") (pin "H2") (pinfunction "IN2_H2") (pintype "input"))
      (node (ref "B02") (pin "H1") (pinfunction "P$2_H1") (pintype "bidirectional"))
    )
    (net (code "222") (name "~{I_MB04}") (class "Default")
      (node (ref "A02") (pin "L1") (pinfunction "P$2_L1") (pintype "bidirectional"))
      (node (ref "A06") (pin "L1") (pinfunction "CATHODE_L1") (pintype "passive"))
      (node (ref "A08") (pin "U2") (pinfunction "IN2_U2") (pintype "input"))
      (node (ref "B02") (pin "L1") (pinfunction "P$2_L1") (pintype "bidirectional"))
    )
    (net (code "223") (name "~{I_MB05}") (class "Default")
      (node (ref "A02") (pin "P1") (pinfunction "P$2_P1") (pintype "bidirectional"))
      (node (ref "A06") (pin "P1") (pinfunction "CATHODE_P1") (pintype "passive"))
      (node (ref "A09") (pin "N2") (pinfunction "IN2_N2") (pintype "input"))
      (node (ref "B02") (pin "P1") (pinfunction "P$2_P1") (pintype "bidirectional"))
    )
    (net (code "224") (name "~{I_MB06}") (class "Default")
      (node (ref "A02") (pin "D2") (pinfunction "P$2_D2") (pintype "bidirectional"))
      (node (ref "A06") (pin "D2") (pinfunction "CATHODE_D2") (pintype "passive"))
      (node (ref "A10") (pin "H2") (pinfunction "IN2_H2") (pintype "input"))
      (node (ref "B02") (pin "D2") (pinfunction "P$2_D2") (pintype "bidirectional"))
    )
    (net (code "225") (name "~{I_MB07}") (class "Default")
      (node (ref "A02") (pin "H2") (pinfunction "P$2_H2") (pintype "bidirectional"))
      (node (ref "A06") (pin "H2") (pinfunction "CATHODE_H2") (pintype "passive"))
      (node (ref "A10") (pin "U2") (pinfunction "IN2_U2") (pintype "input"))
      (node (ref "B02") (pin "H2") (pinfunction "P$2_H2") (pintype "bidirectional"))
    )
    (net (code "226") (name "~{I_MB08}") (class "Default")
      (node (ref "A02") (pin "M2") (pinfunction "P$2_M2") (pintype "bidirectional"))
      (node (ref "A06") (pin "M2") (pinfunction "CATHODE_M2") (pintype "passive"))
      (node (ref "A11") (pin "N2") (pinfunction "IN2_N2") (pintype "input"))
      (node (ref "B02") (pin "M2") (pinfunction "P$2_M2") (pintype "bidirectional"))
    )
    (net (code "227") (name "~{O_MB03}") (class "Default")
      (node (ref "A08") (pin "D2") (pinfunction "OUT_D2") (pintype "output"))
      (node (ref "A15") (pin "K2") (pinfunction "P$2_K2") (pintype "bidirectional"))
    )
    (net (code "228") (name "~{O_MB04}") (class "Default")
      (node (ref "A08") (pin "S2") (pinfunction "OUT_S2") (pintype "output"))
      (node (ref "A15") (pin "P2") (pinfunction "P$2_P2") (pintype "bidirectional"))
    )
    (net (code "229") (name "~{O_MB05}") (class "Default")
      (node (ref "A09") (pin "K2") (pinfunction "OUT_K2") (pintype "output"))
      (node (ref "A15") (pin "T2") (pinfunction "P$2_T2") (pintype "bidirectional"))
    )
    (net (code "230") (name "~{O_MB06}") (class "Default")
      (node (ref "A10") (pin "D2") (pinfunction "OUT_D2") (pintype "output"))
      (node (ref "A16") (pin "D2") (pinfunction "P$2_D2") (pintype "bidirectional"))
    )
    (net (code "231") (name "~{O_MB07}") (class "Default")
      (node (ref "A10") (pin "S2") (pinfunction "OUT_S2") (pintype "output"))
      (node (ref "A16") (pin "H2") (pinfunction "P$2_H2") (pintype "bidirectional"))
    )
    (net (code "232") (name "~{O_MB08}") (class "Default")
      (node (ref "A11") (pin "K2") (pinfunction "OUT_K2") (pintype "output"))
      (node (ref "A16") (pin "M2") (pinfunction "P$2_M2") (pintype "bidirectional"))
    )
  )
)
